# 19_2_Coupled_PP0.net
KiCad netlist of a schematic drawn in Altium Designer
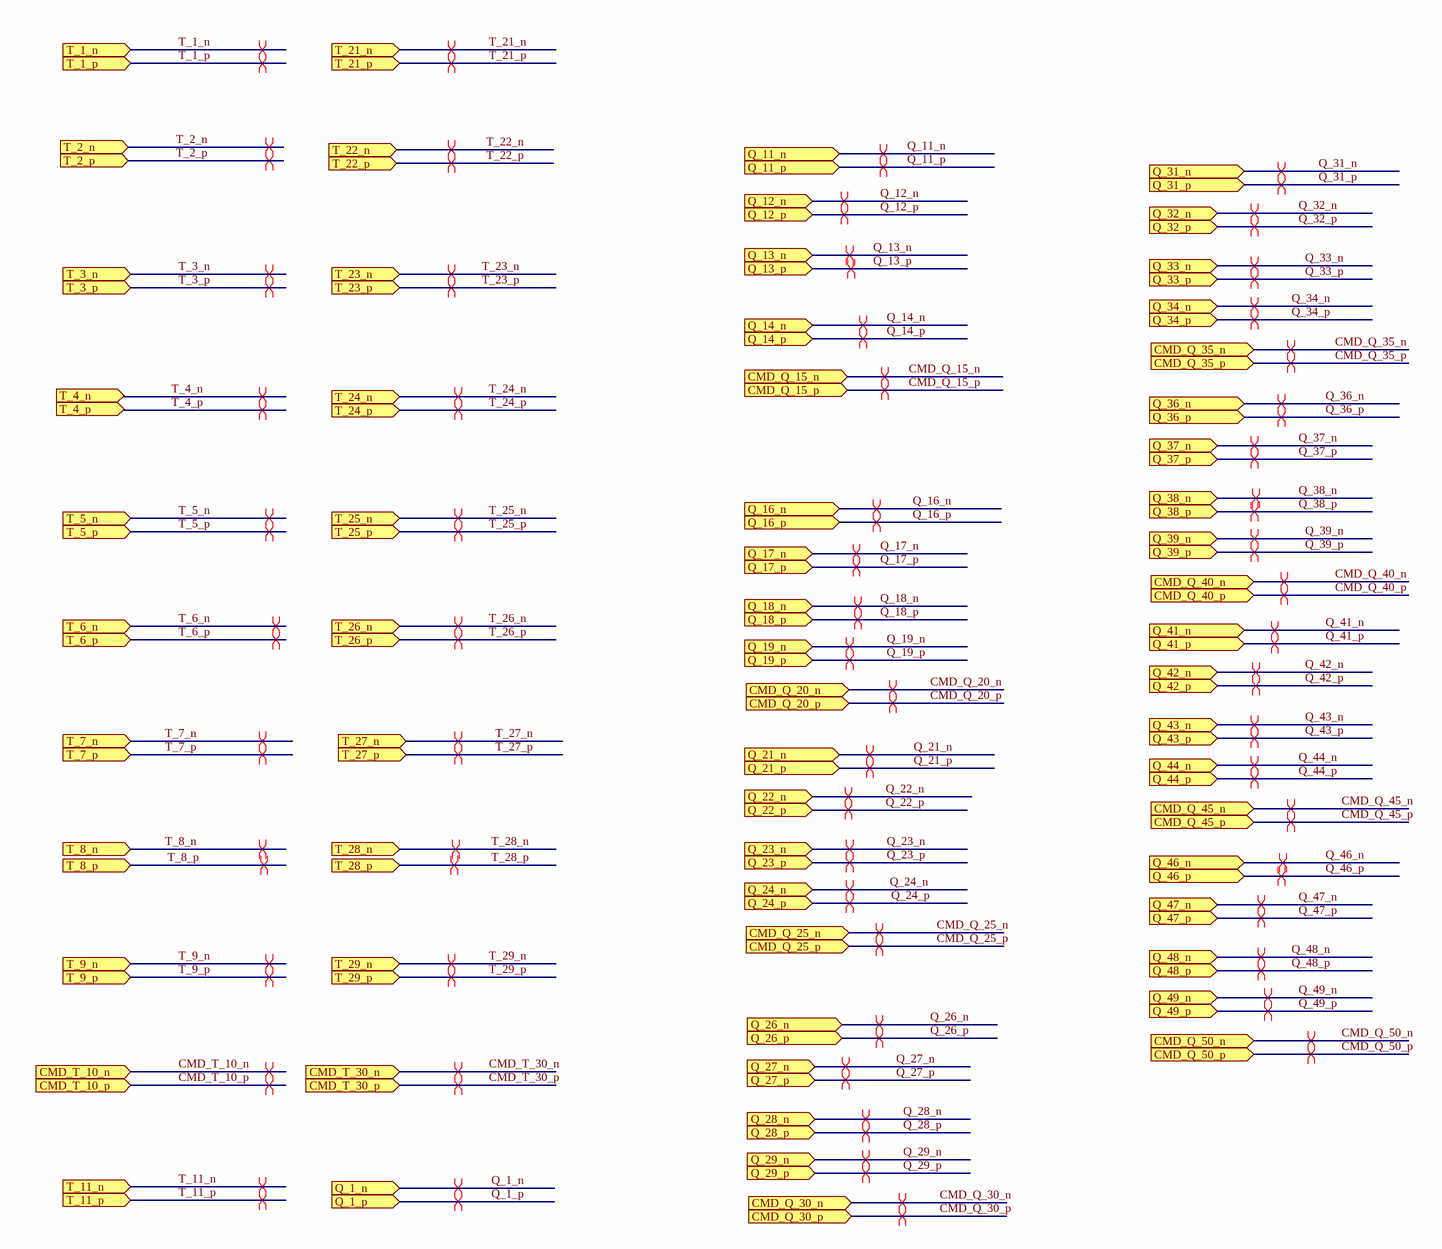
[diagram p0: 19_2_Coupled_PP0.SchDoc, top left]
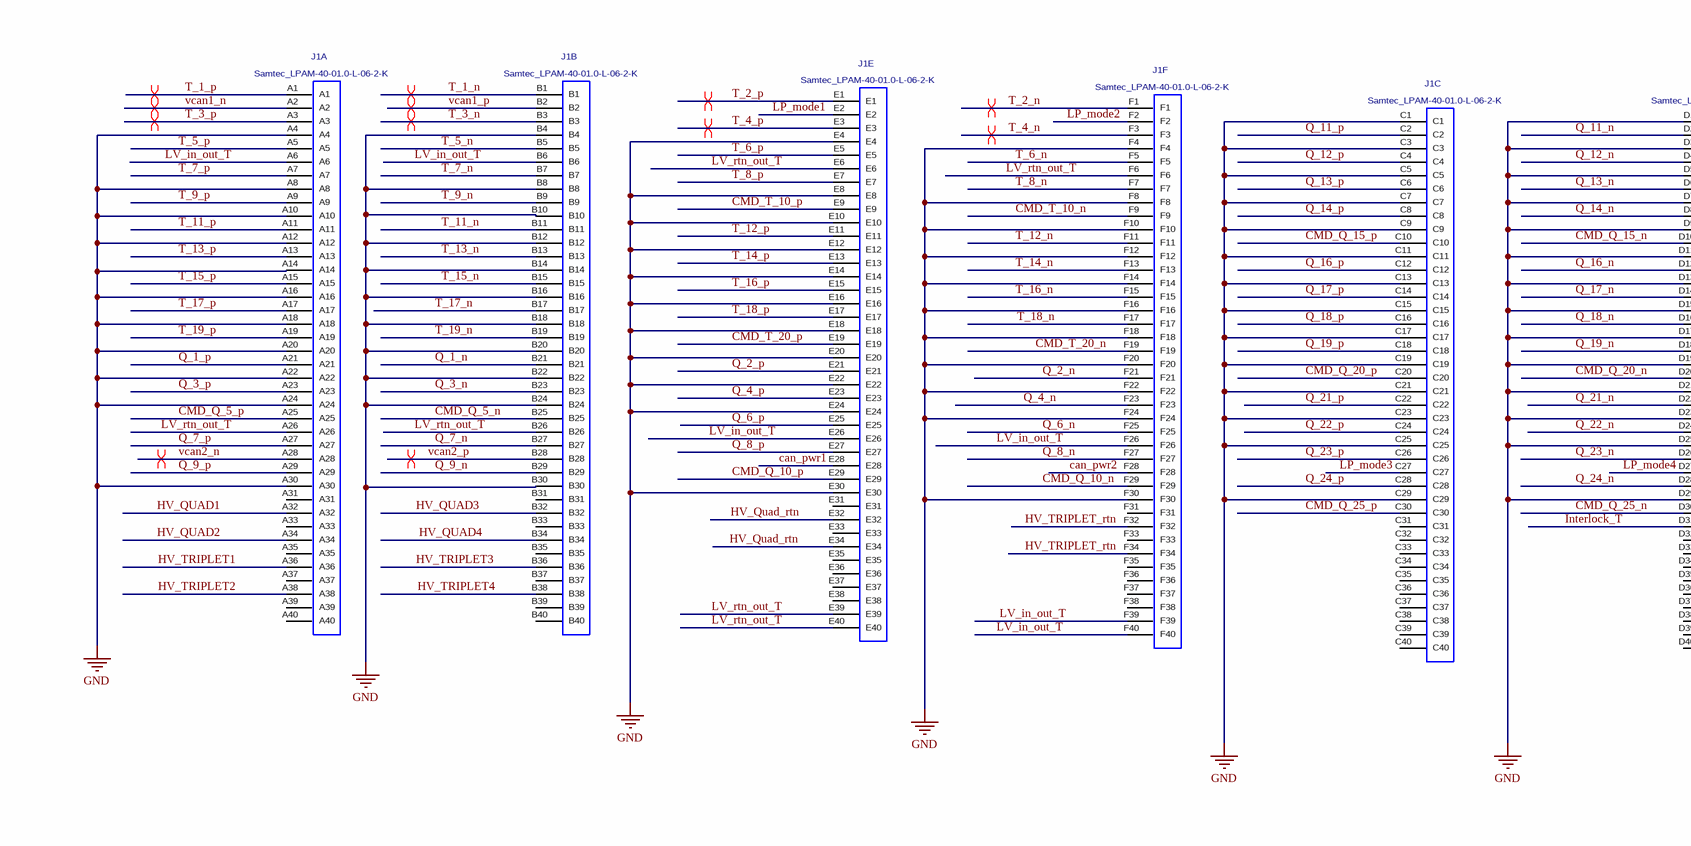
[diagram p1: 19_2_Coupled_PP0.SchDoc, top middle]
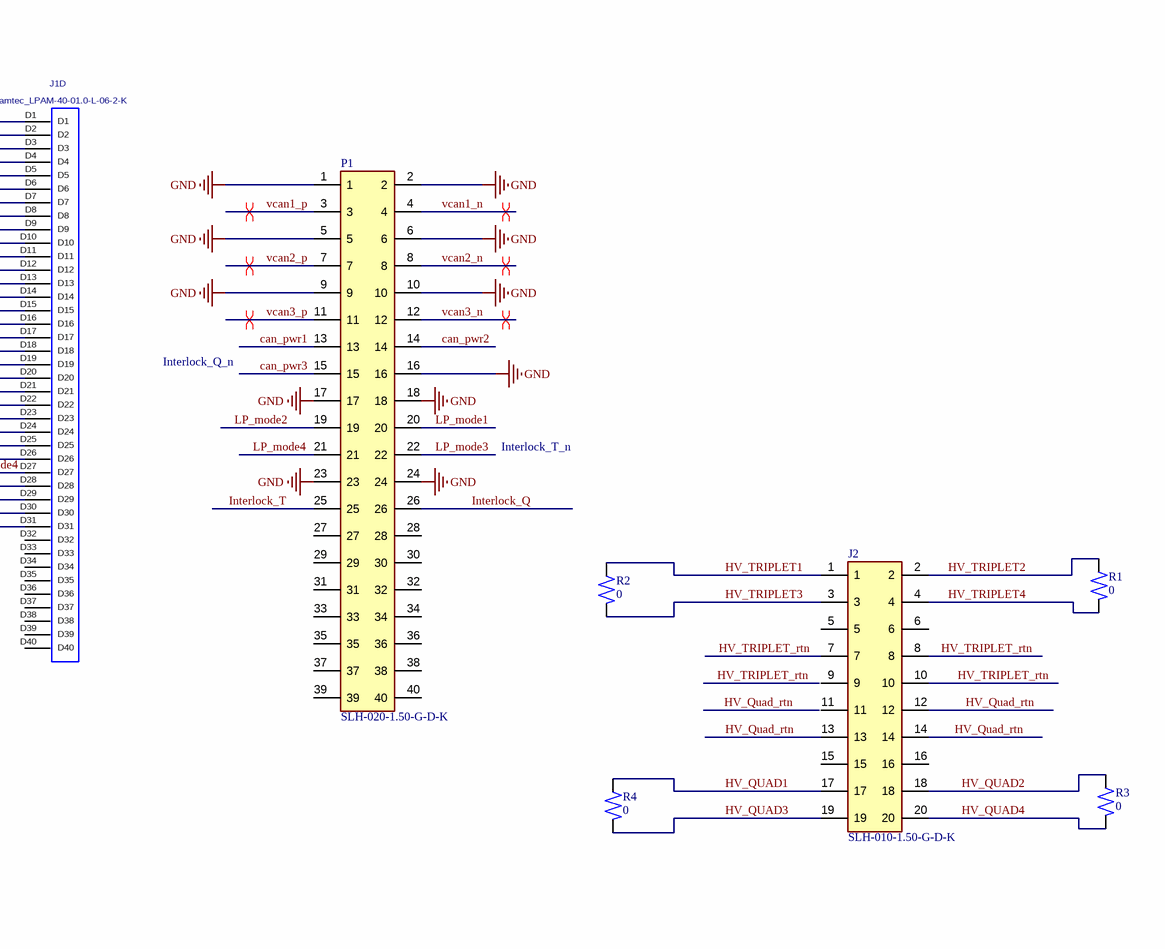
[diagram p2: 19_2_Coupled_PP0.SchDoc, top right]
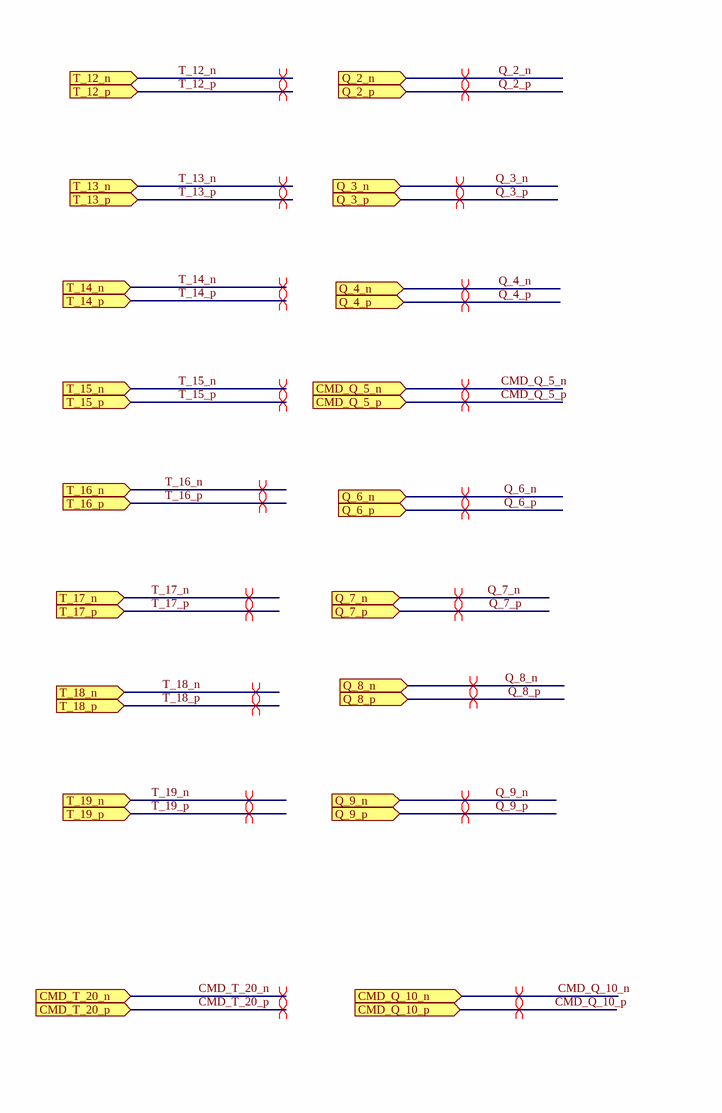
[diagram p3: 19_2_Coupled_PP0.SchDoc, bottom left]
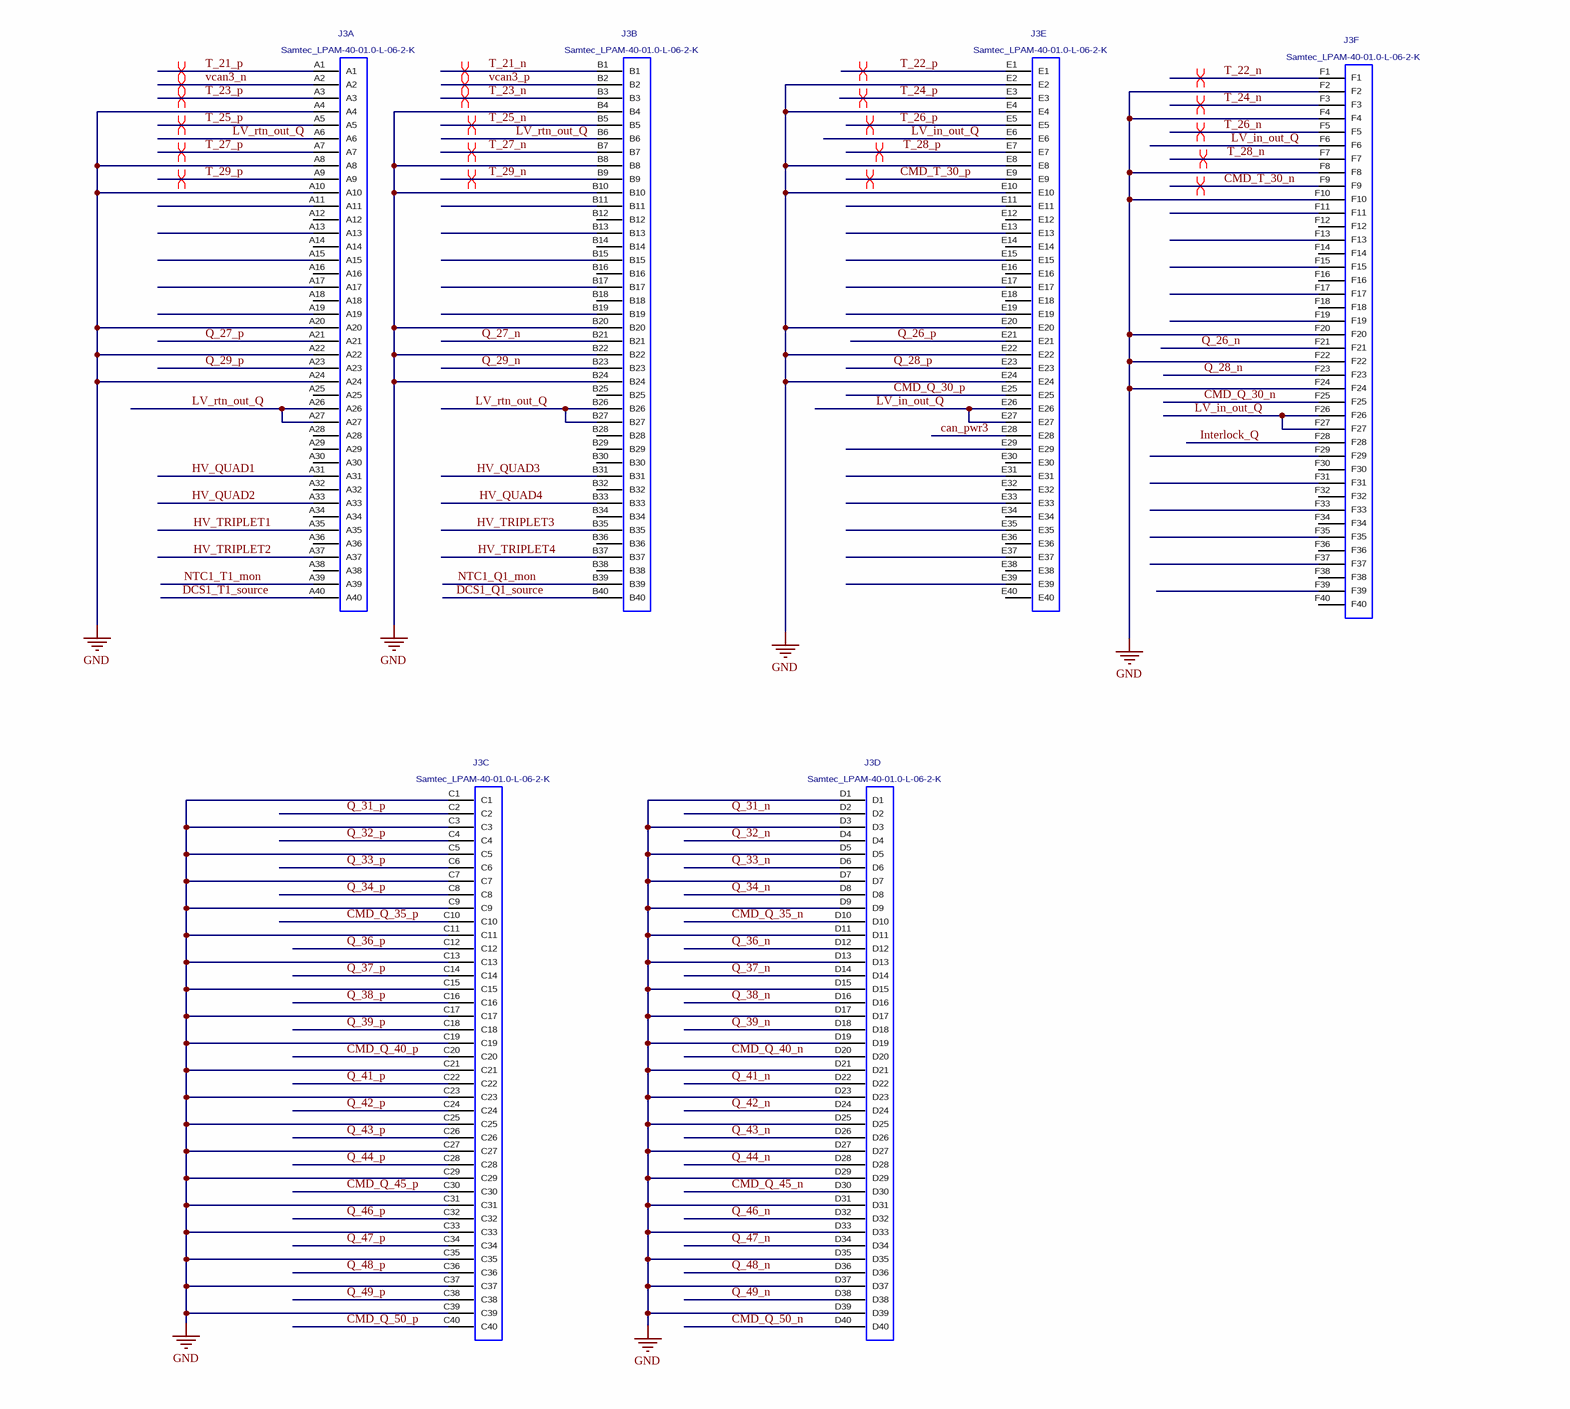
[diagram p4: 19_2_Coupled_PP0.SchDoc, bottom middle]
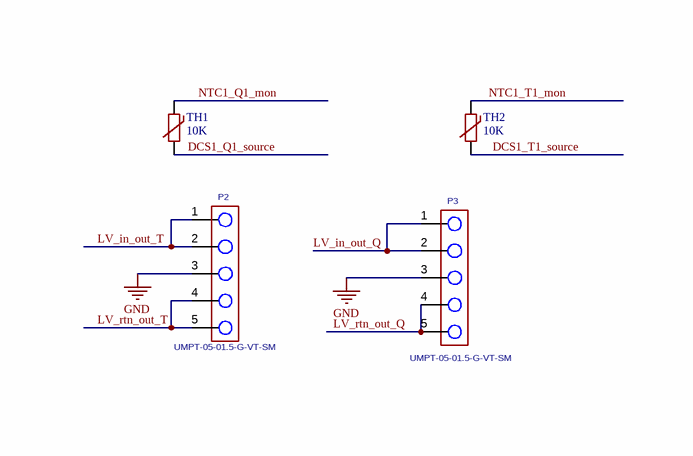
[diagram p5: 19_2_Coupled_PP0.SchDoc, bottom right]

(export (version "E")
  (design (tool "Eeschema 10.0.6"))
  (components
    (comp (ref "J1")
      (value "Samtec_LPAM-40-01.0-L-06-2-K")
      (footprint "Samtec_LPAM_240Pin_V")
      (description "Samtec; LPAM-40-01.0-L-06-2-K, Connector 240Pin Male, LPAM_240Pin_V")
      (fields
        (field (name "MANUFACTURER") "SAMTEC")
        (field (name "MANUFACTURER PART NUMBER") "LPAM-04-01.0-L-06-2-K")
      )
      (libsource (lib "yee_sch_lib") (part "Samtec_LPAM-40-01.0-L-06-2-K"))
    )
    (comp (ref "J2")
      (value "SLH-010-1.50-G-D-K")
      (footprint "Samtec_SLH-010-1.50-G-D-K")
      (description "Samtec; SLH-010-1.50-G-D-K, Connetor 20-Pin SMD")
      (fields
        (field (name "MANUFACTURER") "Samtec")
        (field (name "MANUFACTURER PART NUMBER") "SLH-010-1.50-G-D-K")
      )
      (libsource (lib "Atlas_stave") (part "Samtec_SLH-010-1.50-G-D-K"))
    )
    (comp (ref "J3")
      (value "Samtec_LPAM-40-01.0-L-06-2-K")
      (footprint "Samtec_LPAM_240Pin_V")
      (description "Samtec; LPAM-40-01.0-L-06-2-K, Connector 240Pin Male, LPAM_240Pin_V")
      (fields
        (field (name "MANUFACTURER") "SAMTEC")
        (field (name "MANUFACTURER PART NUMBER") "LPAM-04-01.0-L-06-2-K")
      )
      (libsource (lib "yee_sch_lib") (part "Samtec_LPAM-40-01.0-L-06-2-K"))
    )
    (comp (ref "P1")
      (value "SLH-020-1.50-G-D-K")
      (footprint "Samtec_SLH-020-1.50-G-D-K")
      (description "Samtec; SLH-020-1.50-G-D-K, Connetor 40-Pin SMD")
      (fields
        (field (name "MANUFACTURER") "Samtec")
        (field (name "MANUFACTURER PART NUMBER") "SLH-020-1.50-G-D-K")
      )
      (libsource (lib "Atlas_stave") (part "Samtec_SLH-020-1.50-G-D-K"))
    )
    (comp (ref "P2")
      (value "UMPT-05-01.5-G-VT-SM")
      (footprint "Samtec_UMPT_5P_V")
      (description "Samtec; UMPT-05-01.5-G-VT-SM, Male Connector 5-Pin, UMPT_5P_V")
      (fields (field (name "MANUFACTURER") "SAMTEC"))
      (libsource (lib "yee_sch_lib") (part "Samtec_UMPT-05-01.5-G-VT-SM"))
    )
    (comp (ref "P3")
      (value "UMPT-05-01.5-G-VT-SM")
      (footprint "Samtec_UMPT_5P_V")
      (description "Samtec; UMPT-05-01.5-G-VT-SM, Male Connector 5-Pin, UMPT_5P_V")
      (fields (field (name "MANUFACTURER") "SAMTEC"))
      (libsource (lib "yee_sch_lib") (part "Samtec_UMPT-05-01.5-G-VT-SM"))
    )
    (comp (ref "R1")
      (value "0")
      (footprint "SM0402")
      (description "Vishay; CRCW04020000Z0ED, CHIP RESISTOR, 0 OHMS 1%, SM0402")
      (fields
        (field (name "MANUFACTURER") "VISHAY")
        (field (name "MANUFACTURER PART NUMBER") "CRCW04020000Z0ED")
      )
      (libsource (lib "yee_sch_lib") (part "R04020000"))
    )
    (comp (ref "R2")
      (value "0")
      (footprint "SM0402")
      (description "Vishay; CRCW04020000Z0ED, CHIP RESISTOR, 0 OHMS 1%, SM0402")
      (fields
        (field (name "MANUFACTURER") "VISHAY")
        (field (name "MANUFACTURER PART NUMBER") "CRCW04020000Z0ED")
      )
      (libsource (lib "yee_sch_lib") (part "R04020000"))
    )
    (comp (ref "R3")
      (value "0")
      (footprint "SM0402")
      (description "Vishay; CRCW04020000Z0ED, CHIP RESISTOR, 0 OHMS 1%, SM0402")
      (fields
        (field (name "MANUFACTURER") "VISHAY")
        (field (name "MANUFACTURER PART NUMBER") "CRCW04020000Z0ED")
      )
      (libsource (lib "yee_sch_lib") (part "R04020000"))
    )
    (comp (ref "R4")
      (value "0")
      (footprint "SM0402")
      (description "Vishay; CRCW04020000Z0ED, CHIP RESISTOR, 0 OHMS 1%, SM0402")
      (fields
        (field (name "MANUFACTURER") "VISHAY")
        (field (name "MANUFACTURER PART NUMBER") "CRCW04020000Z0ED")
      )
      (libsource (lib "yee_sch_lib") (part "R04020000"))
    )
    (comp (ref "TH1")
      (value "10K")
      (footprint "SM0805")
      (description "TE; NTC0805J10K, Thermister NTC 10K 5% 2-Pin, SM0805")
      (fields
        (field (name "MANUFACTURER") "TE Connectivity")
        (field (name "MANUFACTURER PART NUMBER") "NTC0805J10K")
      )
      (libsource (lib "yee_sch_lib") (part "NTC080510K0"))
    )
    (comp (ref "TH2")
      (value "10K")
      (footprint "SM0805")
      (description "TE; NTC0805J10K, Thermister NTC 10K 5% 2-Pin, SM0805")
      (fields
        (field (name "MANUFACTURER") "TE Connectivity")
        (field (name "MANUFACTURER PART NUMBER") "NTC0805J10K")
      )
      (libsource (lib "yee_sch_lib") (part "NTC080510K0"))
    )
  )
  (nets
    (net (code "1") (name "/CMD_Q_5_n") (class "Default")
      (node (ref "J1") (pin "B25") (pinfunction "B25_B25") (pintype "passive"))
    )
    (net (code "2") (name "/CMD_Q_5_p") (class "Default")
      (node (ref "J1") (pin "A25") (pinfunction "A25_A25") (pintype "passive"))
    )
    (net (code "3") (name "/CMD_Q_10_n") (class "Default")
      (node (ref "J1") (pin "F29") (pinfunction "F29_F29") (pintype "passive"))
    )
    (net (code "4") (name "/CMD_Q_10_p") (class "Default")
      (node (ref "J1") (pin "E29") (pinfunction "E29_E29") (pintype "passive"))
    )
    (net (code "5") (name "/CMD_Q_15_n") (class "Default")
      (node (ref "J1") (pin "D10") (pinfunction "D10_D10") (pintype "passive"))
    )
    (net (code "6") (name "/CMD_Q_15_p") (class "Default")
      (node (ref "J1") (pin "C10") (pinfunction "C10_C10") (pintype "passive"))
    )
    (net (code "7") (name "/CMD_Q_20_n") (class "Default")
      (node (ref "J1") (pin "D20") (pinfunction "D20_D20") (pintype "passive"))
    )
    (net (code "8") (name "/CMD_Q_20_p") (class "Default")
      (node (ref "J1") (pin "C20") (pinfunction "C20_C20") (pintype "passive"))
    )
    (net (code "9") (name "/CMD_Q_25_n") (class "Default")
      (node (ref "J1") (pin "D30") (pinfunction "D30_D30") (pintype "passive"))
    )
    (net (code "10") (name "/CMD_Q_25_p") (class "Default")
      (node (ref "J1") (pin "C30") (pinfunction "C30_C30") (pintype "passive"))
    )
    (net (code "11") (name "/CMD_Q_30_n") (class "Default")
      (node (ref "J3") (pin "F25") (pinfunction "F25_F25") (pintype "passive"))
    )
    (net (code "12") (name "/CMD_Q_30_p") (class "Default")
      (node (ref "J3") (pin "E25") (pinfunction "E25_E25") (pintype "passive"))
    )
    (net (code "13") (name "/CMD_Q_35_n") (class "Default")
      (node (ref "J3") (pin "D10") (pinfunction "D10_D10") (pintype "passive"))
    )
    (net (code "14") (name "/CMD_Q_35_p") (class "Default")
      (node (ref "J3") (pin "C10") (pinfunction "C10_C10") (pintype "passive"))
    )
    (net (code "15") (name "/CMD_Q_40_n") (class "Default")
      (node (ref "J3") (pin "D20") (pinfunction "D20_D20") (pintype "passive"))
    )
    (net (code "16") (name "/CMD_Q_40_p") (class "Default")
      (node (ref "J3") (pin "C20") (pinfunction "C20_C20") (pintype "passive"))
    )
    (net (code "17") (name "/CMD_Q_45_n") (class "Default")
      (node (ref "J3") (pin "D30") (pinfunction "D30_D30") (pintype "passive"))
    )
    (net (code "18") (name "/CMD_Q_45_p") (class "Default")
      (node (ref "J3") (pin "C30") (pinfunction "C30_C30") (pintype "passive"))
    )
    (net (code "19") (name "/CMD_Q_50_n") (class "Default")
      (node (ref "J3") (pin "D40") (pinfunction "D40_D40") (pintype "passive"))
    )
    (net (code "20") (name "/CMD_Q_50_p") (class "Default")
      (node (ref "J3") (pin "C40") (pinfunction "C40_C40") (pintype "passive"))
    )
    (net (code "21") (name "/CMD_T_10_n") (class "Default")
      (node (ref "J1") (pin "F9") (pinfunction "F9_F9") (pintype "passive"))
    )
    (net (code "22") (name "/CMD_T_10_p") (class "Default")
      (node (ref "J1") (pin "E9") (pinfunction "E9_E9") (pintype "passive"))
    )
    (net (code "23") (name "/CMD_T_20_n") (class "Default")
      (node (ref "J1") (pin "F19") (pinfunction "F19_F19") (pintype "passive"))
    )
    (net (code "24") (name "/CMD_T_20_p") (class "Default")
      (node (ref "J1") (pin "E19") (pinfunction "E19_E19") (pintype "passive"))
    )
    (net (code "25") (name "/CMD_T_30_n") (class "Default")
      (node (ref "J3") (pin "F9") (pinfunction "F9_F9") (pintype "passive"))
    )
    (net (code "26") (name "/CMD_T_30_p") (class "Default")
      (node (ref "J3") (pin "E9") (pinfunction "E9_E9") (pintype "passive"))
    )
    (net (code "27") (name "/DCS1_Q1_source") (class "Default")
      (node (ref "J3") (pin "B40") (pinfunction "B40_B40") (pintype "passive"))
      (node (ref "TH1") (pin "2") (pinfunction "N2_2") (pintype "passive"))
    )
    (net (code "28") (name "/DCS1_T1_source") (class "Default")
      (node (ref "J3") (pin "A40") (pinfunction "A40_A40") (pintype "passive"))
      (node (ref "TH2") (pin "2") (pinfunction "N2_2") (pintype "passive"))
    )
    (net (code "29") (name "/HV_QUAD1") (class "Default")
      (node (ref "J1") (pin "A32") (pinfunction "A32_A32") (pintype "passive"))
      (node (ref "J2") (pin "17") (pinfunction "17_17") (pintype "passive"))
      (node (ref "J3") (pin "A31") (pinfunction "A31_A31") (pintype "passive"))
      (node (ref "R4") (pin "1") (pinfunction "N1_1") (pintype "passive"))
    )
    (net (code "30") (name "/HV_QUAD2") (class "Default")
      (node (ref "J1") (pin "A34") (pinfunction "A34_A34") (pintype "passive"))
      (node (ref "J2") (pin "18") (pinfunction "18_18") (pintype "passive"))
      (node (ref "J3") (pin "A33") (pinfunction "A33_A33") (pintype "passive"))
      (node (ref "R3") (pin "1") (pinfunction "N1_1") (pintype "passive"))
    )
    (net (code "31") (name "/HV_QUAD3") (class "Default")
      (node (ref "J1") (pin "B32") (pinfunction "B32_B32") (pintype "passive"))
      (node (ref "J2") (pin "19") (pinfunction "19_19") (pintype "passive"))
      (node (ref "J3") (pin "B31") (pinfunction "B31_B31") (pintype "passive"))
      (node (ref "R4") (pin "2") (pinfunction "N2_2") (pintype "passive"))
    )
    (net (code "32") (name "/HV_QUAD4") (class "Default")
      (node (ref "J1") (pin "B34") (pinfunction "B34_B34") (pintype "passive"))
      (node (ref "J2") (pin "20") (pinfunction "20_20") (pintype "passive"))
      (node (ref "J3") (pin "B33") (pinfunction "B33_B33") (pintype "passive"))
      (node (ref "R3") (pin "2") (pinfunction "N2_2") (pintype "passive"))
    )
    (net (code "33") (name "/HV_Quad_rtn") (class "Default")
      (node (ref "J1") (pin "E32") (pinfunction "E32_E32") (pintype "passive"))
      (node (ref "J1") (pin "E34") (pinfunction "E34_E34") (pintype "passive"))
      (node (ref "J2") (pin "12") (pinfunction "12_12") (pintype "passive"))
      (node (ref "J2") (pin "13") (pinfunction "13_13") (pintype "passive"))
      (node (ref "J2") (pin "14") (pinfunction "14_14") (pintype "passive"))
    )
    (net (code "34") (name "/HV_TRIPLET1") (class "Default")
      (node (ref "J1") (pin "A36") (pinfunction "A36_A36") (pintype "passive"))
      (node (ref "J2") (pin "1") (pinfunction "1_1") (pintype "passive"))
      (node (ref "J3") (pin "A35") (pinfunction "A35_A35") (pintype "passive"))
      (node (ref "R2") (pin "1") (pinfunction "N1_1") (pintype "passive"))
    )
    (net (code "35") (name "/HV_TRIPLET2") (class "Default")
      (node (ref "J1") (pin "A38") (pinfunction "A38_A38") (pintype "passive"))
      (node (ref "J2") (pin "2") (pinfunction "2_2") (pintype "tri_state"))
      (node (ref "J3") (pin "A37") (pinfunction "A37_A37") (pintype "passive"))
      (node (ref "R1") (pin "1") (pinfunction "N1_1") (pintype "passive"))
    )
    (net (code "36") (name "/HV_TRIPLET3") (class "Default")
      (node (ref "J1") (pin "B36") (pinfunction "B36_B36") (pintype "passive"))
      (node (ref "J2") (pin "3") (pinfunction "3_3") (pintype "passive"))
      (node (ref "J3") (pin "B35") (pinfunction "B35_B35") (pintype "passive"))
      (node (ref "R2") (pin "2") (pinfunction "N2_2") (pintype "passive"))
    )
    (net (code "37") (name "/HV_TRIPLET4") (class "Default")
      (node (ref "J1") (pin "B38") (pinfunction "B38_B38") (pintype "passive"))
      (node (ref "J2") (pin "4") (pinfunction "4_4") (pintype "passive"))
      (node (ref "J3") (pin "B37") (pinfunction "B37_B37") (pintype "passive"))
      (node (ref "R1") (pin "2") (pinfunction "N2_2") (pintype "passive"))
    )
    (net (code "38") (name "/HV_TRIPLET_rtn") (class "Default")
      (node (ref "J1") (pin "F32") (pinfunction "F32_F32") (pintype "passive"))
      (node (ref "J1") (pin "F34") (pinfunction "F34_F34") (pintype "passive"))
      (node (ref "J2") (pin "10") (pinfunction "10_10") (pintype "passive"))
      (node (ref "J2") (pin "7") (pinfunction "7_7") (pintype "passive"))
      (node (ref "J2") (pin "8") (pinfunction "8_8") (pintype "passive"))
    )
    (net (code "39") (name "/Interlock_Q") (class "Default")
      (node (ref "J3") (pin "F28") (pinfunction "F28_F28") (pintype "passive"))
      (node (ref "P1") (pin "26") (pinfunction "26_26") (pintype "passive"))
    )
    (net (code "40") (name "/Interlock_T") (class "Default")
      (node (ref "J1") (pin "D31") (pinfunction "D31_D31") (pintype "passive"))
      (node (ref "P1") (pin "25") (pinfunction "25_25") (pintype "passive"))
    )
    (net (code "41") (name "/LP_mode1") (class "Default")
      (node (ref "J1") (pin "E2") (pinfunction "E2_E2") (pintype "passive"))
      (node (ref "P1") (pin "20") (pinfunction "20_20") (pintype "passive"))
    )
    (net (code "42") (name "/LP_mode2") (class "Default")
      (node (ref "J1") (pin "F2") (pinfunction "F2_F2") (pintype "passive"))
      (node (ref "P1") (pin "19") (pinfunction "19_19") (pintype "passive"))
    )
    (net (code "43") (name "/LP_mode3") (class "Default")
      (node (ref "J1") (pin "C27") (pinfunction "C27_C27") (pintype "passive"))
      (node (ref "P1") (pin "22") (pinfunction "22_22") (pintype "passive"))
    )
    (net (code "44") (name "/LP_mode4") (class "Default")
      (node (ref "J1") (pin "D27") (pinfunction "D27_D27") (pintype "passive"))
      (node (ref "P1") (pin "21") (pinfunction "21_21") (pintype "passive"))
    )
    (net (code "45") (name "/LV_in_out_Q") (class "Default")
      (node (ref "J3") (pin "E26") (pinfunction "E26_E26") (pintype "passive"))
      (node (ref "J3") (pin "E27") (pinfunction "E27_E27") (pintype "passive"))
      (node (ref "J3") (pin "E6") (pinfunction "E6_E6") (pintype "passive"))
      (node (ref "J3") (pin "F26") (pinfunction "F26_F26") (pintype "passive"))
      (node (ref "J3") (pin "F27") (pinfunction "F27_F27") (pintype "passive"))
      (node (ref "J3") (pin "F6") (pinfunction "F6_F6") (pintype "passive"))
      (node (ref "P3") (pin "1") (pinfunction "1_1") (pintype "passive"))
      (node (ref "P3") (pin "2") (pinfunction "2_2") (pintype "passive"))
    )
    (net (code "46") (name "/LV_in_out_T") (class "Default")
      (node (ref "J1") (pin "A6") (pinfunction "A6_A6") (pintype "passive"))
      (node (ref "J1") (pin "B6") (pinfunction "B6_B6") (pintype "passive"))
      (node (ref "J1") (pin "E26") (pinfunction "E26_E26") (pintype "passive"))
      (node (ref "J1") (pin "F26") (pinfunction "F26_F26") (pintype "passive"))
      (node (ref "J1") (pin "F39") (pinfunction "F39_F39") (pintype "passive"))
      (node (ref "J1") (pin "F40") (pinfunction "F40_F40") (pintype "passive"))
      (node (ref "P2") (pin "1") (pinfunction "1_1") (pintype "passive"))
      (node (ref "P2") (pin "2") (pinfunction "2_2") (pintype "passive"))
    )
    (net (code "47") (name "/LV_rtn_out_Q") (class "Default")
      (node (ref "J3") (pin "A26") (pinfunction "A26_A26") (pintype "passive"))
      (node (ref "J3") (pin "A27") (pinfunction "A27_A27") (pintype "passive"))
      (node (ref "J3") (pin "A6") (pinfunction "A6_A6") (pintype "passive"))
      (node (ref "J3") (pin "B26") (pinfunction "B26_B26") (pintype "passive"))
      (node (ref "J3") (pin "B27") (pinfunction "B27_B27") (pintype "passive"))
      (node (ref "J3") (pin "B6") (pinfunction "B6_B6") (pintype "passive"))
      (node (ref "P3") (pin "4") (pinfunction "4_4") (pintype "passive"))
      (node (ref "P3") (pin "5") (pinfunction "5_5") (pintype "passive"))
    )
    (net (code "48") (name "/LV_rtn_out_T") (class "Default")
      (node (ref "J1") (pin "A26") (pinfunction "A26_A26") (pintype "passive"))
      (node (ref "J1") (pin "B26") (pinfunction "B26_B26") (pintype "passive"))
      (node (ref "J1") (pin "E39") (pinfunction "E39_E39") (pintype "passive"))
      (node (ref "J1") (pin "E40") (pinfunction "E40_E40") (pintype "passive"))
      (node (ref "J1") (pin "E6") (pinfunction "E6_E6") (pintype "passive"))
      (node (ref "J1") (pin "F6") (pinfunction "F6_F6") (pintype "passive"))
      (node (ref "P2") (pin "4") (pinfunction "4_4") (pintype "passive"))
      (node (ref "P2") (pin "5") (pinfunction "5_5") (pintype "passive"))
    )
    (net (code "49") (name "/NTC1_Q1_mon") (class "Default")
      (node (ref "J3") (pin "B39") (pinfunction "B39_B39") (pintype "passive"))
      (node (ref "TH1") (pin "1") (pinfunction "N1_1") (pintype "passive"))
    )
    (net (code "50") (name "/NTC1_T1_mon") (class "Default")
      (node (ref "J3") (pin "A39") (pinfunction "A39_A39") (pintype "passive"))
      (node (ref "TH2") (pin "1") (pinfunction "N1_1") (pintype "passive"))
    )
    (net (code "51") (name "/Q_1_n") (class "Default")
      (node (ref "J1") (pin "B21") (pinfunction "B21_B21") (pintype "passive"))
    )
    (net (code "52") (name "/Q_1_p") (class "Default")
      (node (ref "J1") (pin "A21") (pinfunction "A21_A21") (pintype "passive"))
    )
    (net (code "53") (name "/Q_2_n") (class "Default")
      (node (ref "J1") (pin "F21") (pinfunction "F21_F21") (pintype "passive"))
    )
    (net (code "54") (name "/Q_2_p") (class "Default")
      (node (ref "J1") (pin "E21") (pinfunction "E21_E21") (pintype "passive"))
    )
    (net (code "55") (name "/Q_3_n") (class "Default")
      (node (ref "J1") (pin "B23") (pinfunction "B23_B23") (pintype "passive"))
    )
    (net (code "56") (name "/Q_3_p") (class "Default")
      (node (ref "J1") (pin "A23") (pinfunction "A23_A23") (pintype "passive"))
    )
    (net (code "57") (name "/Q_4_n") (class "Default")
      (node (ref "J1") (pin "F23") (pinfunction "F23_F23") (pintype "passive"))
    )
    (net (code "58") (name "/Q_4_p") (class "Default")
      (node (ref "J1") (pin "E23") (pinfunction "E23_E23") (pintype "passive"))
    )
    (net (code "59") (name "/Q_6_n") (class "Default")
      (node (ref "J1") (pin "F25") (pinfunction "F25_F25") (pintype "passive"))
    )
    (net (code "60") (name "/Q_6_p") (class "Default")
      (node (ref "J1") (pin "E25") (pinfunction "E25_E25") (pintype "passive"))
    )
    (net (code "61") (name "/Q_7_n") (class "Default")
      (node (ref "J1") (pin "B27") (pinfunction "B27_B27") (pintype "passive"))
    )
    (net (code "62") (name "/Q_7_p") (class "Default")
      (node (ref "J1") (pin "A27") (pinfunction "A27_A27") (pintype "passive"))
    )
    (net (code "63") (name "/Q_8_n") (class "Default")
      (node (ref "J1") (pin "F27") (pinfunction "F27_F27") (pintype "passive"))
    )
    (net (code "64") (name "/Q_8_p") (class "Default")
      (node (ref "J1") (pin "E27") (pinfunction "E27_E27") (pintype "passive"))
    )
    (net (code "65") (name "/Q_9_n") (class "Default")
      (node (ref "J1") (pin "B29") (pinfunction "B29_B29") (pintype "passive"))
    )
    (net (code "66") (name "/Q_9_p") (class "Default")
      (node (ref "J1") (pin "A29") (pinfunction "A29_A29") (pintype "passive"))
    )
    (net (code "67") (name "/Q_11_n") (class "Default")
      (node (ref "J1") (pin "D2") (pinfunction "D2_D2") (pintype "passive"))
    )
    (net (code "68") (name "/Q_11_p") (class "Default")
      (node (ref "J1") (pin "C2") (pinfunction "C2_C2") (pintype "passive"))
    )
    (net (code "69") (name "/Q_12_n") (class "Default")
      (node (ref "J1") (pin "D4") (pinfunction "D4_D4") (pintype "passive"))
    )
    (net (code "70") (name "/Q_12_p") (class "Default")
      (node (ref "J1") (pin "C4") (pinfunction "C4_C4") (pintype "passive"))
    )
    (net (code "71") (name "/Q_13_n") (class "Default")
      (node (ref "J1") (pin "D6") (pinfunction "D6_D6") (pintype "passive"))
    )
    (net (code "72") (name "/Q_13_p") (class "Default")
      (node (ref "J1") (pin "C6") (pinfunction "C6_C6") (pintype "passive"))
    )
    (net (code "73") (name "/Q_14_n") (class "Default")
      (node (ref "J1") (pin "D8") (pinfunction "D8_D8") (pintype "passive"))
    )
    (net (code "74") (name "/Q_14_p") (class "Default")
      (node (ref "J1") (pin "C8") (pinfunction "C8_C8") (pintype "passive"))
    )
    (net (code "75") (name "/Q_16_n") (class "Default")
      (node (ref "J1") (pin "D12") (pinfunction "D12_D12") (pintype "passive"))
    )
    (net (code "76") (name "/Q_16_p") (class "Default")
      (node (ref "J1") (pin "C12") (pinfunction "C12_C12") (pintype "passive"))
    )
    (net (code "77") (name "/Q_17_n") (class "Default")
      (node (ref "J1") (pin "D14") (pinfunction "D14_D14") (pintype "passive"))
    )
    (net (code "78") (name "/Q_17_p") (class "Default")
      (node (ref "J1") (pin "C14") (pinfunction "C14_C14") (pintype "passive"))
    )
    (net (code "79") (name "/Q_18_n") (class "Default")
      (node (ref "J1") (pin "D16") (pinfunction "D16_D16") (pintype "passive"))
    )
    (net (code "80") (name "/Q_18_p") (class "Default")
      (node (ref "J1") (pin "C16") (pinfunction "C16_C16") (pintype "passive"))
    )
    (net (code "81") (name "/Q_19_n") (class "Default")
      (node (ref "J1") (pin "D18") (pinfunction "D18_D18") (pintype "passive"))
    )
    (net (code "82") (name "/Q_19_p") (class "Default")
      (node (ref "J1") (pin "C18") (pinfunction "C18_C18") (pintype "passive"))
    )
    (net (code "83") (name "/Q_21_n") (class "Default")
      (node (ref "J1") (pin "D22") (pinfunction "D22_D22") (pintype "passive"))
    )
    (net (code "84") (name "/Q_21_p") (class "Default")
      (node (ref "J1") (pin "C22") (pinfunction "C22_C22") (pintype "passive"))
    )
    (net (code "85") (name "/Q_22_n") (class "Default")
      (node (ref "J1") (pin "D24") (pinfunction "D24_D24") (pintype "passive"))
    )
    (net (code "86") (name "/Q_22_p") (class "Default")
      (node (ref "J1") (pin "C24") (pinfunction "C24_C24") (pintype "passive"))
    )
    (net (code "87") (name "/Q_23_n") (class "Default")
      (node (ref "J1") (pin "D26") (pinfunction "D26_D26") (pintype "passive"))
    )
    (net (code "88") (name "/Q_23_p") (class "Default")
      (node (ref "J1") (pin "C26") (pinfunction "C26_C26") (pintype "passive"))
    )
    (net (code "89") (name "/Q_24_n") (class "Default")
      (node (ref "J1") (pin "D28") (pinfunction "D28_D28") (pintype "passive"))
    )
    (net (code "90") (name "/Q_24_p") (class "Default")
      (node (ref "J1") (pin "C28") (pinfunction "C28_C28") (pintype "passive"))
    )
    (net (code "91") (name "/Q_26_n") (class "Default")
      (node (ref "J3") (pin "F21") (pinfunction "F21_F21") (pintype "passive"))
    )
    (net (code "92") (name "/Q_26_p") (class "Default")
      (node (ref "J3") (pin "E21") (pinfunction "E21_E21") (pintype "passive"))
    )
    (net (code "93") (name "/Q_27_n") (class "Default")
      (node (ref "J3") (pin "B21") (pinfunction "B21_B21") (pintype "passive"))
    )
    (net (code "94") (name "/Q_27_p") (class "Default")
      (node (ref "J3") (pin "A21") (pinfunction "A21_A21") (pintype "passive"))
    )
    (net (code "95") (name "/Q_28_n") (class "Default")
      (node (ref "J3") (pin "F23") (pinfunction "F23_F23") (pintype "passive"))
    )
    (net (code "96") (name "/Q_28_p") (class "Default")
      (node (ref "J3") (pin "E23") (pinfunction "E23_E23") (pintype "passive"))
    )
    (net (code "97") (name "/Q_29_n") (class "Default")
      (node (ref "J3") (pin "B23") (pinfunction "B23_B23") (pintype "passive"))
    )
    (net (code "98") (name "/Q_29_p") (class "Default")
      (node (ref "J3") (pin "A23") (pinfunction "A23_A23") (pintype "passive"))
    )
    (net (code "99") (name "/Q_31_n") (class "Default")
      (node (ref "J3") (pin "D2") (pinfunction "D2_D2") (pintype "passive"))
    )
    (net (code "100") (name "/Q_31_p") (class "Default")
      (node (ref "J3") (pin "C2") (pinfunction "C2_C2") (pintype "passive"))
    )
    (net (code "101") (name "/Q_32_n") (class "Default")
      (node (ref "J3") (pin "D4") (pinfunction "D4_D4") (pintype "passive"))
    )
    (net (code "102") (name "/Q_32_p") (class "Default")
      (node (ref "J3") (pin "C4") (pinfunction "C4_C4") (pintype "passive"))
    )
    (net (code "103") (name "/Q_33_n") (class "Default")
      (node (ref "J3") (pin "D6") (pinfunction "D6_D6") (pintype "passive"))
    )
    (net (code "104") (name "/Q_33_p") (class "Default")
      (node (ref "J3") (pin "C6") (pinfunction "C6_C6") (pintype "passive"))
    )
    (net (code "105") (name "/Q_34_n") (class "Default")
      (node (ref "J3") (pin "D8") (pinfunction "D8_D8") (pintype "passive"))
    )
    (net (code "106") (name "/Q_34_p") (class "Default")
      (node (ref "J3") (pin "C8") (pinfunction "C8_C8") (pintype "passive"))
    )
    (net (code "107") (name "/Q_36_n") (class "Default")
      (node (ref "J3") (pin "D12") (pinfunction "D12_D12") (pintype "passive"))
    )
    (net (code "108") (name "/Q_36_p") (class "Default")
      (node (ref "J3") (pin "C12") (pinfunction "C12_C12") (pintype "passive"))
    )
    (net (code "109") (name "/Q_37_n") (class "Default")
      (node (ref "J3") (pin "D14") (pinfunction "D14_D14") (pintype "passive"))
    )
    (net (code "110") (name "/Q_37_p") (class "Default")
      (node (ref "J3") (pin "C14") (pinfunction "C14_C14") (pintype "passive"))
    )
    (net (code "111") (name "/Q_38_n") (class "Default")
      (node (ref "J3") (pin "D16") (pinfunction "D16_D16") (pintype "passive"))
    )
    (net (code "112") (name "/Q_38_p") (class "Default")
      (node (ref "J3") (pin "C16") (pinfunction "C16_C16") (pintype "passive"))
    )
    (net (code "113") (name "/Q_39_n") (class "Default")
      (node (ref "J3") (pin "D18") (pinfunction "D18_D18") (pintype "passive"))
    )
    (net (code "114") (name "/Q_39_p") (class "Default")
      (node (ref "J3") (pin "C18") (pinfunction "C18_C18") (pintype "passive"))
    )
    (net (code "115") (name "/Q_41_n") (class "Default")
      (node (ref "J3") (pin "D22") (pinfunction "D22_D22") (pintype "passive"))
    )
    (net (code "116") (name "/Q_41_p") (class "Default")
      (node (ref "J3") (pin "C22") (pinfunction "C22_C22") (pintype "passive"))
    )
    (net (code "117") (name "/Q_42_n") (class "Default")
      (node (ref "J3") (pin "D24") (pinfunction "D24_D24") (pintype "passive"))
    )
    (net (code "118") (name "/Q_42_p") (class "Default")
      (node (ref "J3") (pin "C24") (pinfunction "C24_C24") (pintype "passive"))
    )
    (net (code "119") (name "/Q_43_n") (class "Default")
      (node (ref "J3") (pin "D26") (pinfunction "D26_D26") (pintype "passive"))
    )
    (net (code "120") (name "/Q_43_p") (class "Default")
      (node (ref "J3") (pin "C26") (pinfunction "C26_C26") (pintype "passive"))
    )
    (net (code "121") (name "/Q_44_n") (class "Default")
      (node (ref "J3") (pin "D28") (pinfunction "D28_D28") (pintype "passive"))
    )
    (net (code "122") (name "/Q_44_p") (class "Default")
      (node (ref "J3") (pin "C28") (pinfunction "C28_C28") (pintype "passive"))
    )
    (net (code "123") (name "/Q_46_n") (class "Default")
      (node (ref "J3") (pin "D32") (pinfunction "D32_D32") (pintype "passive"))
    )
    (net (code "124") (name "/Q_46_p") (class "Default")
      (node (ref "J3") (pin "C32") (pinfunction "C32_C32") (pintype "passive"))
    )
    (net (code "125") (name "/Q_47_n") (class "Default")
      (node (ref "J3") (pin "D34") (pinfunction "D34_D34") (pintype "passive"))
    )
    (net (code "126") (name "/Q_47_p") (class "Default")
      (node (ref "J3") (pin "C34") (pinfunction "C34_C34") (pintype "passive"))
    )
    (net (code "127") (name "/Q_48_n") (class "Default")
      (node (ref "J3") (pin "D36") (pinfunction "D36_D36") (pintype "passive"))
    )
    (net (code "128") (name "/Q_48_p") (class "Default")
      (node (ref "J3") (pin "C36") (pinfunction "C36_C36") (pintype "passive"))
    )
    (net (code "129") (name "/Q_49_n") (class "Default")
      (node (ref "J3") (pin "D38") (pinfunction "D38_D38") (pintype "passive"))
    )
    (net (code "130") (name "/Q_49_p") (class "Default")
      (node (ref "J3") (pin "C38") (pinfunction "C38_C38") (pintype "passive"))
    )
    (net (code "131") (name "/T_1_n") (class "Default")
      (node (ref "J1") (pin "B1") (pinfunction "B1_B1") (pintype "passive"))
    )
    (net (code "132") (name "/T_1_p") (class "Default")
      (node (ref "J1") (pin "A1") (pinfunction "A1_A1") (pintype "passive"))
    )
    (net (code "133") (name "/T_2_n") (class "Default")
      (node (ref "J1") (pin "F1") (pinfunction "F1_F1") (pintype "passive"))
    )
    (net (code "134") (name "/T_2_p") (class "Default")
      (node (ref "J1") (pin "E1") (pinfunction "E1_E1") (pintype "passive"))
    )
    (net (code "135") (name "/T_3_n") (class "Default")
      (node (ref "J1") (pin "B3") (pinfunction "B3_B3") (pintype "passive"))
    )
    (net (code "136") (name "/T_3_p") (class "Default")
      (node (ref "J1") (pin "A3") (pinfunction "A3_A3") (pintype "passive"))
    )
    (net (code "137") (name "/T_4_n") (class "Default")
      (node (ref "J1") (pin "F3") (pinfunction "F3_F3") (pintype "passive"))
    )
    (net (code "138") (name "/T_4_p") (class "Default")
      (node (ref "J1") (pin "E3") (pinfunction "E3_E3") (pintype "passive"))
    )
    (net (code "139") (name "/T_5_n") (class "Default")
      (node (ref "J1") (pin "B5") (pinfunction "B5_B5") (pintype "passive"))
    )
    (net (code "140") (name "/T_5_p") (class "Default")
      (node (ref "J1") (pin "A5") (pinfunction "A5_A5") (pintype "passive"))
    )
    (net (code "141") (name "/T_6_n") (class "Default")
      (node (ref "J1") (pin "F5") (pinfunction "F5_F5") (pintype "passive"))
    )
    (net (code "142") (name "/T_6_p") (class "Default")
      (node (ref "J1") (pin "E5") (pinfunction "E5_E5") (pintype "passive"))
    )
    (net (code "143") (name "/T_7_n") (class "Default")
      (node (ref "J1") (pin "B7") (pinfunction "B7_B7") (pintype "passive"))
    )
    (net (code "144") (name "/T_7_p") (class "Default")
      (node (ref "J1") (pin "A7") (pinfunction "A7_A7") (pintype "passive"))
    )
    (net (code "145") (name "/T_8_n") (class "Default")
      (node (ref "J1") (pin "F7") (pinfunction "F7_F7") (pintype "passive"))
    )
    (net (code "146") (name "/T_8_p") (class "Default")
      (node (ref "J1") (pin "E7") (pinfunction "E7_E7") (pintype "passive"))
    )
    (net (code "147") (name "/T_9_n") (class "Default")
      (node (ref "J1") (pin "B9") (pinfunction "B9_B9") (pintype "passive"))
    )
    (net (code "148") (name "/T_9_p") (class "Default")
      (node (ref "J1") (pin "A9") (pinfunction "A9_A9") (pintype "passive"))
    )
    (net (code "149") (name "/T_11_n") (class "Default")
      (node (ref "J1") (pin "B11") (pinfunction "B11_B11") (pintype "passive"))
    )
    (net (code "150") (name "/T_11_p") (class "Default")
      (node (ref "J1") (pin "A11") (pinfunction "A11_A11") (pintype "passive"))
    )
    (net (code "151") (name "/T_12_n") (class "Default")
      (node (ref "J1") (pin "F11") (pinfunction "F11_F11") (pintype "passive"))
    )
    (net (code "152") (name "/T_12_p") (class "Default")
      (node (ref "J1") (pin "E11") (pinfunction "E11_E11") (pintype "passive"))
    )
    (net (code "153") (name "/T_13_n") (class "Default")
      (node (ref "J1") (pin "B13") (pinfunction "B13_B13") (pintype "passive"))
    )
    (net (code "154") (name "/T_13_p") (class "Default")
      (node (ref "J1") (pin "A13") (pinfunction "A13_A13") (pintype "passive"))
    )
    (net (code "155") (name "/T_14_n") (class "Default")
      (node (ref "J1") (pin "F13") (pinfunction "F13_F13") (pintype "passive"))
    )
    (net (code "156") (name "/T_14_p") (class "Default")
      (node (ref "J1") (pin "E13") (pinfunction "E13_E13") (pintype "passive"))
    )
    (net (code "157") (name "/T_15_n") (class "Default")
      (node (ref "J1") (pin "B15") (pinfunction "B15_B15") (pintype "passive"))
    )
    (net (code "158") (name "/T_15_p") (class "Default")
      (node (ref "J1") (pin "A15") (pinfunction "A15_A15") (pintype "passive"))
    )
    (net (code "159") (name "/T_16_n") (class "Default")
      (node (ref "J1") (pin "F15") (pinfunction "F15_F15") (pintype "passive"))
    )
    (net (code "160") (name "/T_16_p") (class "Default")
      (node (ref "J1") (pin "E15") (pinfunction "E15_E15") (pintype "passive"))
    )
    (net (code "161") (name "/T_17_n") (class "Default")
      (node (ref "J1") (pin "B17") (pinfunction "B17_B17") (pintype "passive"))
    )
    (net (code "162") (name "/T_17_p") (class "Default")
      (node (ref "J1") (pin "A17") (pinfunction "A17_A17") (pintype "passive"))
    )
    (net (code "163") (name "/T_18_n") (class "Default")
      (node (ref "J1") (pin "F17") (pinfunction "F17_F17") (pintype "passive"))
    )
    (net (code "164") (name "/T_18_p") (class "Default")
      (node (ref "J1") (pin "E17") (pinfunction "E17_E17") (pintype "passive"))
    )
    (net (code "165") (name "/T_19_n") (class "Default")
      (node (ref "J1") (pin "B19") (pinfunction "B19_B19") (pintype "passive"))
    )
    (net (code "166") (name "/T_19_p") (class "Default")
      (node (ref "J1") (pin "A19") (pinfunction "A19_A19") (pintype "passive"))
    )
    (net (code "167") (name "/T_21_n") (class "Default")
      (node (ref "J3") (pin "B1") (pinfunction "B1_B1") (pintype "passive"))
    )
    (net (code "168") (name "/T_21_p") (class "Default")
      (node (ref "J3") (pin "A1") (pinfunction "A1_A1") (pintype "passive"))
    )
    (net (code "169") (name "/T_22_n") (class "Default")
      (node (ref "J3") (pin "F1") (pinfunction "F1_F1") (pintype "passive"))
    )
    (net (code "170") (name "/T_22_p") (class "Default")
      (node (ref "J3") (pin "E1") (pinfunction "E1_E1") (pintype "passive"))
    )
    (net (code "171") (name "/T_23_n") (class "Default")
      (node (ref "J3") (pin "B3") (pinfunction "B3_B3") (pintype "passive"))
    )
    (net (code "172") (name "/T_23_p") (class "Default")
      (node (ref "J3") (pin "A3") (pinfunction "A3_A3") (pintype "passive"))
    )
    (net (code "173") (name "/T_24_n") (class "Default")
      (node (ref "J3") (pin "F3") (pinfunction "F3_F3") (pintype "passive"))
    )
    (net (code "174") (name "/T_24_p") (class "Default")
      (node (ref "J3") (pin "E3") (pinfunction "E3_E3") (pintype "passive"))
    )
    (net (code "175") (name "/T_25_n") (class "Default")
      (node (ref "J3") (pin "B5") (pinfunction "B5_B5") (pintype "passive"))
    )
    (net (code "176") (name "/T_25_p") (class "Default")
      (node (ref "J3") (pin "A5") (pinfunction "A5_A5") (pintype "passive"))
    )
    (net (code "177") (name "/T_26_n") (class "Default")
      (node (ref "J3") (pin "F5") (pinfunction "F5_F5") (pintype "passive"))
    )
    (net (code "178") (name "/T_26_p") (class "Default")
      (node (ref "J3") (pin "E5") (pinfunction "E5_E5") (pintype "passive"))
    )
    (net (code "179") (name "/T_27_n") (class "Default")
      (node (ref "J3") (pin "B7") (pinfunction "B7_B7") (pintype "passive"))
    )
    (net (code "180") (name "/T_27_p") (class "Default")
      (node (ref "J3") (pin "A7") (pinfunction "A7_A7") (pintype "passive"))
    )
    (net (code "181") (name "/T_28_n") (class "Default")
      (node (ref "J3") (pin "F7") (pinfunction "F7_F7") (pintype "passive"))
    )
    (net (code "182") (name "/T_28_p") (class "Default")
      (node (ref "J3") (pin "E7") (pinfunction "E7_E7") (pintype "passive"))
    )
    (net (code "183") (name "/T_29_n") (class "Default")
      (node (ref "J3") (pin "B9") (pinfunction "B9_B9") (pintype "passive"))
    )
    (net (code "184") (name "/T_29_p") (class "Default")
      (node (ref "J3") (pin "A9") (pinfunction "A9_A9") (pintype "passive"))
    )
    (net (code "185") (name "/can_pwr1") (class "Default")
      (node (ref "J1") (pin "E28") (pinfunction "E28_E28") (pintype "passive"))
      (node (ref "P1") (pin "13") (pinfunction "13_13") (pintype "passive"))
    )
    (net (code "186") (name "/can_pwr2") (class "Default")
      (node (ref "J1") (pin "F28") (pinfunction "F28_F28") (pintype "passive"))
      (node (ref "P1") (pin "14") (pinfunction "14_14") (pintype "passive"))
    )
    (net (code "187") (name "/can_pwr3") (class "Default")
      (node (ref "J3") (pin "E28") (pinfunction "E28_E28") (pintype "passive"))
      (node (ref "P1") (pin "15") (pinfunction "15_15") (pintype "passive"))
    )
    (net (code "188") (name "/vcan1_n") (class "Default")
      (node (ref "J1") (pin "A2") (pinfunction "A2_A2") (pintype "passive"))
      (node (ref "P1") (pin "4") (pinfunction "4_4") (pintype "passive"))
    )
    (net (code "189") (name "/vcan1_p") (class "Default")
      (node (ref "J1") (pin "B2") (pinfunction "B2_B2") (pintype "passive"))
      (node (ref "P1") (pin "3") (pinfunction "3_3") (pintype "passive"))
    )
    (net (code "190") (name "/vcan2_n") (class "Default")
      (node (ref "J1") (pin "A28") (pinfunction "A28_A28") (pintype "passive"))
      (node (ref "P1") (pin "8") (pinfunction "8_8") (pintype "passive"))
    )
    (net (code "191") (name "/vcan2_p") (class "Default")
      (node (ref "J1") (pin "B28") (pinfunction "B28_B28") (pintype "passive"))
      (node (ref "P1") (pin "7") (pinfunction "7_7") (pintype "passive"))
    )
    (net (code "192") (name "/vcan3_n") (class "Default")
      (node (ref "J3") (pin "A2") (pinfunction "A2_A2") (pintype "passive"))
      (node (ref "P1") (pin "12") (pinfunction "12_12") (pintype "passive"))
    )
    (net (code "193") (name "/vcan3_p") (class "Default")
      (node (ref "J3") (pin "B2") (pinfunction "B2_B2") (pintype "passive"))
      (node (ref "P1") (pin "11") (pinfunction "11_11") (pintype "passive"))
    )
    (net (code "194") (name "GND") (class "Default")
      (node (ref "J1") (pin "A10") (pinfunction "A10_A10") (pintype "passive"))
      (node (ref "J1") (pin "A12") (pinfunction "A12_A12") (pintype "passive"))
      (node (ref "J1") (pin "A14") (pinfunction "A14_A14") (pintype "passive"))
      (node (ref "J1") (pin "A16") (pinfunction "A16_A16") (pintype "passive"))
      (node (ref "J1") (pin "A18") (pinfunction "A18_A18") (pintype "passive"))
      (node (ref "J1") (pin "A20") (pinfunction "A20_A20") (pintype "passive"))
      (node (ref "J1") (pin "A22") (pinfunction "A22_A22") (pintype "passive"))
      (node (ref "J1") (pin "A24") (pinfunction "A24_A24") (pintype "passive"))
      (node (ref "J1") (pin "A30") (pinfunction "A30_A30") (pintype "passive"))
      (node (ref "J1") (pin "A4") (pinfunction "A4_A4") (pintype "passive"))
      (node (ref "J1") (pin "A8") (pinfunction "A8_A8") (pintype "passive"))
      (node (ref "J1") (pin "B10") (pinfunction "B10_B10") (pintype "passive"))
      (node (ref "J1") (pin "B12") (pinfunction "B12_B12") (pintype "passive"))
      (node (ref "J1") (pin "B14") (pinfunction "B14_B14") (pintype "passive"))
      (node (ref "J1") (pin "B16") (pinfunction "B16_B16") (pintype "passive"))
      (node (ref "J1") (pin "B18") (pinfunction "B18_B18") (pintype "passive"))
      (node (ref "J1") (pin "B20") (pinfunction "B20_B20") (pintype "passive"))
      (node (ref "J1") (pin "B22") (pinfunction "B22_B22") (pintype "passive"))
      (node (ref "J1") (pin "B24") (pinfunction "B24_B24") (pintype "passive"))
      (node (ref "J1") (pin "B30") (pinfunction "B30_B30") (pintype "passive"))
      (node (ref "J1") (pin "B4") (pinfunction "B4_B4") (pintype "passive"))
      (node (ref "J1") (pin "B8") (pinfunction "B8_B8") (pintype "passive"))
      (node (ref "J1") (pin "C1") (pinfunction "C1_C1") (pintype "passive"))
      (node (ref "J1") (pin "C11") (pinfunction "C11_C11") (pintype "passive"))
      (node (ref "J1") (pin "C13") (pinfunction "C13_C13") (pintype "passive"))
      (node (ref "J1") (pin "C15") (pinfunction "C15_C15") (pintype "passive"))
      (node (ref "J1") (pin "C17") (pinfunction "C17_C17") (pintype "passive"))
      (node (ref "J1") (pin "C19") (pinfunction "C19_C19") (pintype "passive"))
      (node (ref "J1") (pin "C21") (pinfunction "C21_C21") (pintype "passive"))
      (node (ref "J1") (pin "C23") (pinfunction "C23_C23") (pintype "passive"))
      (node (ref "J1") (pin "C25") (pinfunction "C25_C25") (pintype "passive"))
      (node (ref "J1") (pin "C29") (pinfunction "C29_C29") (pintype "passive"))
      (node (ref "J1") (pin "C3") (pinfunction "C3_C3") (pintype "passive"))
      (node (ref "J1") (pin "C5") (pinfunction "C5_C5") (pintype "passive"))
      (node (ref "J1") (pin "C7") (pinfunction "C7_C7") (pintype "passive"))
      (node (ref "J1") (pin "C9") (pinfunction "C9_C9") (pintype "passive"))
      (node (ref "J1") (pin "D1") (pinfunction "D1_D1") (pintype "passive"))
      (node (ref "J1") (pin "D11") (pinfunction "D11_D11") (pintype "passive"))
      (node (ref "J1") (pin "D13") (pinfunction "D13_D13") (pintype "passive"))
      (node (ref "J1") (pin "D15") (pinfunction "D15_D15") (pintype "passive"))
      (node (ref "J1") (pin "D17") (pinfunction "D17_D17") (pintype "passive"))
      (node (ref "J1") (pin "D19") (pinfunction "D19_D19") (pintype "passive"))
      (node (ref "J1") (pin "D21") (pinfunction "D21_D21") (pintype "passive"))
      (node (ref "J1") (pin "D23") (pinfunction "D23_D23") (pintype "passive"))
      (node (ref "J1") (pin "D25") (pinfunction "D25_D25") (pintype "passive"))
      (node (ref "J1") (pin "D29") (pinfunction "D29_D29") (pintype "passive"))
      (node (ref "J1") (pin "D3") (pinfunction "D3_D3") (pintype "passive"))
      (node (ref "J1") (pin "D5") (pinfunction "D5_D5") (pintype "passive"))
      (node (ref "J1") (pin "D7") (pinfunction "D7_D7") (pintype "passive"))
      (node (ref "J1") (pin "D9") (pinfunction "D9_D9") (pintype "passive"))
      (node (ref "J1") (pin "E10") (pinfunction "E10_E10") (pintype "passive"))
      (node (ref "J1") (pin "E12") (pinfunction "E12_E12") (pintype "passive"))
      (node (ref "J1") (pin "E14") (pinfunction "E14_E14") (pintype "passive"))
      (node (ref "J1") (pin "E16") (pinfunction "E16_E16") (pintype "passive"))
      (node (ref "J1") (pin "E18") (pinfunction "E18_E18") (pintype "passive"))
      (node (ref "J1") (pin "E20") (pinfunction "E20_E20") (pintype "passive"))
      (node (ref "J1") (pin "E22") (pinfunction "E22_E22") (pintype "passive"))
      (node (ref "J1") (pin "E24") (pinfunction "E24_E24") (pintype "passive"))
      (node (ref "J1") (pin "E30") (pinfunction "E30_E30") (pintype "passive"))
      (node (ref "J1") (pin "E4") (pinfunction "E4_E4") (pintype "passive"))
      (node (ref "J1") (pin "E8") (pinfunction "E8_E8") (pintype "passive"))
      (node (ref "J1") (pin "F10") (pinfunction "F10_F10") (pintype "passive"))
      (node (ref "J1") (pin "F12") (pinfunction "F12_F12") (pintype "passive"))
      (node (ref "J1") (pin "F14") (pinfunction "F14_F14") (pintype "passive"))
      (node (ref "J1") (pin "F16") (pinfunction "F16_F16") (pintype "passive"))
      (node (ref "J1") (pin "F18") (pinfunction "F18_F18") (pintype "passive"))
      (node (ref "J1") (pin "F20") (pinfunction "F20_F20") (pintype "passive"))
      (node (ref "J1") (pin "F22") (pinfunction "F22_F22") (pintype "passive"))
      (node (ref "J1") (pin "F24") (pinfunction "F24_F24") (pintype "passive"))
      (node (ref "J1") (pin "F30") (pinfunction "F30_F30") (pintype "passive"))
      (node (ref "J1") (pin "F4") (pinfunction "F4_F4") (pintype "passive"))
      (node (ref "J1") (pin "F8") (pinfunction "F8_F8") (pintype "passive"))
      (node (ref "J3") (pin "A10") (pinfunction "A10_A10") (pintype "passive"))
      (node (ref "J3") (pin "A20") (pinfunction "A20_A20") (pintype "passive"))
      (node (ref "J3") (pin "A22") (pinfunction "A22_A22") (pintype "passive"))
      (node (ref "J3") (pin "A24") (pinfunction "A24_A24") (pintype "passive"))
      (node (ref "J3") (pin "A4") (pinfunction "A4_A4") (pintype "passive"))
      (node (ref "J3") (pin "A8") (pinfunction "A8_A8") (pintype "passive"))
      (node (ref "J3") (pin "B10") (pinfunction "B10_B10") (pintype "passive"))
      (node (ref "J3") (pin "B20") (pinfunction "B20_B20") (pintype "passive"))
      (node (ref "J3") (pin "B22") (pinfunction "B22_B22") (pintype "passive"))
      (node (ref "J3") (pin "B24") (pinfunction "B24_B24") (pintype "passive"))
      (node (ref "J3") (pin "B4") (pinfunction "B4_B4") (pintype "passive"))
      (node (ref "J3") (pin "B8") (pinfunction "B8_B8") (pintype "passive"))
      (node (ref "J3") (pin "C1") (pinfunction "C1_C1") (pintype "passive"))
      (node (ref "J3") (pin "C11") (pinfunction "C11_C11") (pintype "passive"))
      (node (ref "J3") (pin "C13") (pinfunction "C13_C13") (pintype "passive"))
      (node (ref "J3") (pin "C15") (pinfunction "C15_C15") (pintype "passive"))
      (node (ref "J3") (pin "C17") (pinfunction "C17_C17") (pintype "passive"))
      (node (ref "J3") (pin "C19") (pinfunction "C19_C19") (pintype "passive"))
      (node (ref "J3") (pin "C21") (pinfunction "C21_C21") (pintype "passive"))
      (node (ref "J3") (pin "C23") (pinfunction "C23_C23") (pintype "passive"))
      (node (ref "J3") (pin "C25") (pinfunction "C25_C25") (pintype "passive"))
      (node (ref "J3") (pin "C27") (pinfunction "C27_C27") (pintype "passive"))
      (node (ref "J3") (pin "C29") (pinfunction "C29_C29") (pintype "passive"))
      (node (ref "J3") (pin "C3") (pinfunction "C3_C3") (pintype "passive"))
      (node (ref "J3") (pin "C31") (pinfunction "C31_C31") (pintype "passive"))
      (node (ref "J3") (pin "C33") (pinfunction "C33_C33") (pintype "passive"))
      (node (ref "J3") (pin "C35") (pinfunction "C35_C35") (pintype "passive"))
      (node (ref "J3") (pin "C37") (pinfunction "C37_C37") (pintype "passive"))
      (node (ref "J3") (pin "C39") (pinfunction "C39_C39") (pintype "passive"))
      (node (ref "J3") (pin "C5") (pinfunction "C5_C5") (pintype "passive"))
      (node (ref "J3") (pin "C7") (pinfunction "C7_C7") (pintype "passive"))
      (node (ref "J3") (pin "C9") (pinfunction "C9_C9") (pintype "passive"))
      (node (ref "J3") (pin "D1") (pinfunction "D1_D1") (pintype "passive"))
      (node (ref "J3") (pin "D11") (pinfunction "D11_D11") (pintype "passive"))
      (node (ref "J3") (pin "D13") (pinfunction "D13_D13") (pintype "passive"))
      (node (ref "J3") (pin "D15") (pinfunction "D15_D15") (pintype "passive"))
      (node (ref "J3") (pin "D17") (pinfunction "D17_D17") (pintype "passive"))
      (node (ref "J3") (pin "D19") (pinfunction "D19_D19") (pintype "passive"))
      (node (ref "J3") (pin "D21") (pinfunction "D21_D21") (pintype "passive"))
      (node (ref "J3") (pin "D23") (pinfunction "D23_D23") (pintype "passive"))
      (node (ref "J3") (pin "D25") (pinfunction "D25_D25") (pintype "passive"))
      (node (ref "J3") (pin "D27") (pinfunction "D27_D27") (pintype "passive"))
      (node (ref "J3") (pin "D29") (pinfunction "D29_D29") (pintype "passive"))
      (node (ref "J3") (pin "D3") (pinfunction "D3_D3") (pintype "passive"))
      (node (ref "J3") (pin "D31") (pinfunction "D31_D31") (pintype "passive"))
      (node (ref "J3") (pin "D33") (pinfunction "D33_D33") (pintype "passive"))
      (node (ref "J3") (pin "D35") (pinfunction "D35_D35") (pintype "passive"))
      (node (ref "J3") (pin "D37") (pinfunction "D37_D37") (pintype "passive"))
      (node (ref "J3") (pin "D39") (pinfunction "D39_D39") (pintype "passive"))
      (node (ref "J3") (pin "D5") (pinfunction "D5_D5") (pintype "passive"))
      (node (ref "J3") (pin "D7") (pinfunction "D7_D7") (pintype "passive"))
      (node (ref "J3") (pin "D9") (pinfunction "D9_D9") (pintype "passive"))
      (node (ref "J3") (pin "E10") (pinfunction "E10_E10") (pintype "passive"))
      (node (ref "J3") (pin "E2") (pinfunction "E2_E2") (pintype "passive"))
      (node (ref "J3") (pin "E20") (pinfunction "E20_E20") (pintype "passive"))
      (node (ref "J3") (pin "E22") (pinfunction "E22_E22") (pintype "passive"))
      (node (ref "J3") (pin "E24") (pinfunction "E24_E24") (pintype "passive"))
      (node (ref "J3") (pin "E4") (pinfunction "E4_E4") (pintype "passive"))
      (node (ref "J3") (pin "E8") (pinfunction "E8_E8") (pintype "passive"))
      (node (ref "J3") (pin "F10") (pinfunction "F10_F10") (pintype "passive"))
      (node (ref "J3") (pin "F2") (pinfunction "F2_F2") (pintype "passive"))
      (node (ref "J3") (pin "F20") (pinfunction "F20_F20") (pintype "passive"))
      (node (ref "J3") (pin "F22") (pinfunction "F22_F22") (pintype "passive"))
      (node (ref "J3") (pin "F24") (pinfunction "F24_F24") (pintype "passive"))
      (node (ref "J3") (pin "F4") (pinfunction "F4_F4") (pintype "passive"))
      (node (ref "J3") (pin "F8") (pinfunction "F8_F8") (pintype "passive"))
      (node (ref "P1") (pin "1") (pinfunction "1_1") (pintype "passive"))
      (node (ref "P1") (pin "10") (pinfunction "10_10") (pintype "passive"))
      (node (ref "P1") (pin "16") (pinfunction "16_16") (pintype "passive"))
      (node (ref "P1") (pin "17") (pinfunction "17_17") (pintype "passive"))
      (node (ref "P1") (pin "18") (pinfunction "18_18") (pintype "passive"))
      (node (ref "P1") (pin "2") (pinfunction "2_2") (pintype "passive"))
      (node (ref "P1") (pin "23") (pinfunction "23_23") (pintype "passive"))
      (node (ref "P1") (pin "24") (pinfunction "24_24") (pintype "passive"))
      (node (ref "P1") (pin "5") (pinfunction "5_5") (pintype "passive"))
      (node (ref "P1") (pin "6") (pinfunction "6_6") (pintype "power_in"))
      (node (ref "P1") (pin "9") (pinfunction "9_9") (pintype "passive"))
      (node (ref "P2") (pin "3") (pinfunction "3_3") (pintype "passive"))
      (node (ref "P3") (pin "3") (pinfunction "3_3") (pintype "passive"))
    )
    (net (code "195") (name "unconnected-(J1-PadA31)") (class "Default")
      (node (ref "J1") (pin "A31") (pinfunction "A31_A31") (pintype "passive"))
    )
    (net (code "196") (name "unconnected-(J1-PadA33)") (class "Default")
      (node (ref "J1") (pin "A33") (pinfunction "A33_A33") (pintype "passive"))
    )
    (net (code "197") (name "unconnected-(J1-PadA35)") (class "Default")
      (node (ref "J1") (pin "A35") (pinfunction "A35_A35") (pintype "passive"))
    )
    (net (code "198") (name "unconnected-(J1-PadA37)") (class "Default")
      (node (ref "J1") (pin "A37") (pinfunction "A37_A37") (pintype "passive"))
    )
    (net (code "199") (name "unconnected-(J1-PadA39)") (class "Default")
      (node (ref "J1") (pin "A39") (pinfunction "A39_A39") (pintype "passive"))
    )
    (net (code "200") (name "unconnected-(J1-PadA40)") (class "Default")
      (node (ref "J1") (pin "A40") (pinfunction "A40_A40") (pintype "passive"))
    )
    (net (code "201") (name "unconnected-(J1-PadB31)") (class "Default")
      (node (ref "J1") (pin "B31") (pinfunction "B31_B31") (pintype "passive"))
    )
    (net (code "202") (name "unconnected-(J1-PadB33)") (class "Default")
      (node (ref "J1") (pin "B33") (pinfunction "B33_B33") (pintype "passive"))
    )
    (net (code "203") (name "unconnected-(J1-PadB35)") (class "Default")
      (node (ref "J1") (pin "B35") (pinfunction "B35_B35") (pintype "passive"))
    )
    (net (code "204") (name "unconnected-(J1-PadB37)") (class "Default")
      (node (ref "J1") (pin "B37") (pinfunction "B37_B37") (pintype "passive"))
    )
    (net (code "205") (name "unconnected-(J1-PadB39)") (class "Default")
      (node (ref "J1") (pin "B39") (pinfunction "B39_B39") (pintype "passive"))
    )
    (net (code "206") (name "unconnected-(J1-PadB40)") (class "Default")
      (node (ref "J1") (pin "B40") (pinfunction "B40_B40") (pintype "passive"))
    )
    (net (code "207") (name "unconnected-(J1-PadC31)") (class "Default")
      (node (ref "J1") (pin "C31") (pinfunction "C31_C31") (pintype "passive"))
    )
    (net (code "208") (name "unconnected-(J1-PadC32)") (class "Default")
      (node (ref "J1") (pin "C32") (pinfunction "C32_C32") (pintype "passive"))
    )
    (net (code "209") (name "unconnected-(J1-PadC33)") (class "Default")
      (node (ref "J1") (pin "C33") (pinfunction "C33_C33") (pintype "passive"))
    )
    (net (code "210") (name "unconnected-(J1-PadC34)") (class "Default")
      (node (ref "J1") (pin "C34") (pinfunction "C34_C34") (pintype "passive"))
    )
    (net (code "211") (name "unconnected-(J1-PadC35)") (class "Default")
      (node (ref "J1") (pin "C35") (pinfunction "C35_C35") (pintype "passive"))
    )
    (net (code "212") (name "unconnected-(J1-PadC36)") (class "Default")
      (node (ref "J1") (pin "C36") (pinfunction "C36_C36") (pintype "passive"))
    )
    (net (code "213") (name "unconnected-(J1-PadC37)") (class "Default")
      (node (ref "J1") (pin "C37") (pinfunction "C37_C37") (pintype "passive"))
    )
    (net (code "214") (name "unconnected-(J1-PadC38)") (class "Default")
      (node (ref "J1") (pin "C38") (pinfunction "C38_C38") (pintype "passive"))
    )
    (net (code "215") (name "unconnected-(J1-PadC39)") (class "Default")
      (node (ref "J1") (pin "C39") (pinfunction "C39_C39") (pintype "passive"))
    )
    (net (code "216") (name "unconnected-(J1-PadC40)") (class "Default")
      (node (ref "J1") (pin "C40") (pinfunction "C40_C40") (pintype "passive"))
    )
    (net (code "217") (name "unconnected-(J1-PadD32)") (class "Default")
      (node (ref "J1") (pin "D32") (pinfunction "D32_D32") (pintype "passive"))
    )
    (net (code "218") (name "unconnected-(J1-PadD33)") (class "Default")
      (node (ref "J1") (pin "D33") (pinfunction "D33_D33") (pintype "passive"))
    )
    (net (code "219") (name "unconnected-(J1-PadD34)") (class "Default")
      (node (ref "J1") (pin "D34") (pinfunction "D34_D34") (pintype "passive"))
    )
    (net (code "220") (name "unconnected-(J1-PadD35)") (class "Default")
      (node (ref "J1") (pin "D35") (pinfunction "D35_D35") (pintype "passive"))
    )
    (net (code "221") (name "unconnected-(J1-PadD36)") (class "Default")
      (node (ref "J1") (pin "D36") (pinfunction "D36_D36") (pintype "passive"))
    )
    (net (code "222") (name "unconnected-(J1-PadD37)") (class "Default")
      (node (ref "J1") (pin "D37") (pinfunction "D37_D37") (pintype "passive"))
    )
    (net (code "223") (name "unconnected-(J1-PadD38)") (class "Default")
      (node (ref "J1") (pin "D38") (pinfunction "D38_D38") (pintype "passive"))
    )
    (net (code "224") (name "unconnected-(J1-PadD39)") (class "Default")
      (node (ref "J1") (pin "D39") (pinfunction "D39_D39") (pintype "passive"))
    )
    (net (code "225") (name "unconnected-(J1-PadD40)") (class "Default")
      (node (ref "J1") (pin "D40") (pinfunction "D40_D40") (pintype "passive"))
    )
    (net (code "226") (name "unconnected-(J1-PadE31)") (class "Default")
      (node (ref "J1") (pin "E31") (pinfunction "E31_E31") (pintype "passive"))
    )
    (net (code "227") (name "unconnected-(J1-PadE33)") (class "Default")
      (node (ref "J1") (pin "E33") (pinfunction "E33_E33") (pintype "passive"))
    )
    (net (code "228") (name "unconnected-(J1-PadE35)") (class "Default")
      (node (ref "J1") (pin "E35") (pinfunction "E35_E35") (pintype "passive"))
    )
    (net (code "229") (name "unconnected-(J1-PadE36)") (class "Default")
      (node (ref "J1") (pin "E36") (pinfunction "E36_E36") (pintype "passive"))
    )
    (net (code "230") (name "unconnected-(J1-PadE37)") (class "Default")
      (node (ref "J1") (pin "E37") (pinfunction "E37_E37") (pintype "passive"))
    )
    (net (code "231") (name "unconnected-(J1-PadE38)") (class "Default")
      (node (ref "J1") (pin "E38") (pinfunction "E38_E38") (pintype "passive"))
    )
    (net (code "232") (name "unconnected-(J1-PadF31)") (class "Default")
      (node (ref "J1") (pin "F31") (pinfunction "F31_F31") (pintype "passive"))
    )
    (net (code "233") (name "unconnected-(J1-PadF33)") (class "Default")
      (node (ref "J1") (pin "F33") (pinfunction "F33_F33") (pintype "passive"))
    )
    (net (code "234") (name "unconnected-(J1-PadF35)") (class "Default")
      (node (ref "J1") (pin "F35") (pinfunction "F35_F35") (pintype "passive"))
    )
    (net (code "235") (name "unconnected-(J1-PadF36)") (class "Default")
      (node (ref "J1") (pin "F36") (pinfunction "F36_F36") (pintype "passive"))
    )
    (net (code "236") (name "unconnected-(J1-PadF37)") (class "Default")
      (node (ref "J1") (pin "F37") (pinfunction "F37_F37") (pintype "passive"))
    )
    (net (code "237") (name "unconnected-(J1-PadF38)") (class "Default")
      (node (ref "J1") (pin "F38") (pinfunction "F38_F38") (pintype "passive"))
    )
    (net (code "238") (name "unconnected-(J2-Pad5)") (class "Default")
      (node (ref "J2") (pin "5") (pinfunction "5_5") (pintype "passive"))
    )
    (net (code "239") (name "unconnected-(J2-Pad6)") (class "Default")
      (node (ref "J2") (pin "6") (pinfunction "6_6") (pintype "passive"))
    )
    (net (code "240") (name "unconnected-(J2-Pad9)") (class "Default")
      (node (ref "J2") (pin "9") (pinfunction "9_9") (pintype "passive"))
    )
    (net (code "241") (name "unconnected-(J2-Pad11)") (class "Default")
      (node (ref "J2") (pin "11") (pinfunction "11_11") (pintype "passive"))
    )
    (net (code "242") (name "unconnected-(J2-Pad15)") (class "Default")
      (node (ref "J2") (pin "15") (pinfunction "15_15") (pintype "passive"))
    )
    (net (code "243") (name "unconnected-(J2-Pad16)") (class "Default")
      (node (ref "J2") (pin "16") (pinfunction "16_16") (pintype "passive"))
    )
    (net (code "244") (name "unconnected-(J3-PadA11)") (class "Default")
      (node (ref "J3") (pin "A11") (pinfunction "A11_A11") (pintype "passive"))
    )
    (net (code "245") (name "unconnected-(J3-PadA12)") (class "Default")
      (node (ref "J3") (pin "A12") (pinfunction "A12_A12") (pintype "passive"))
    )
    (net (code "246") (name "unconnected-(J3-PadA13)") (class "Default")
      (node (ref "J3") (pin "A13") (pinfunction "A13_A13") (pintype "passive"))
    )
    (net (code "247") (name "unconnected-(J3-PadA14)") (class "Default")
      (node (ref "J3") (pin "A14") (pinfunction "A14_A14") (pintype "passive"))
    )
    (net (code "248") (name "unconnected-(J3-PadA15)") (class "Default")
      (node (ref "J3") (pin "A15") (pinfunction "A15_A15") (pintype "passive"))
    )
    (net (code "249") (name "unconnected-(J3-PadA16)") (class "Default")
      (node (ref "J3") (pin "A16") (pinfunction "A16_A16") (pintype "passive"))
    )
    (net (code "250") (name "unconnected-(J3-PadA17)") (class "Default")
      (node (ref "J3") (pin "A17") (pinfunction "A17_A17") (pintype "passive"))
    )
    (net (code "251") (name "unconnected-(J3-PadA18)") (class "Default")
      (node (ref "J3") (pin "A18") (pinfunction "A18_A18") (pintype "passive"))
    )
    (net (code "252") (name "unconnected-(J3-PadA19)") (class "Default")
      (node (ref "J3") (pin "A19") (pinfunction "A19_A19") (pintype "passive"))
    )
    (net (code "253") (name "unconnected-(J3-PadA25)") (class "Default")
      (node (ref "J3") (pin "A25") (pinfunction "A25_A25") (pintype "passive"))
    )
    (net (code "254") (name "unconnected-(J3-PadA28)") (class "Default")
      (node (ref "J3") (pin "A28") (pinfunction "A28_A28") (pintype "passive"))
    )
    (net (code "255") (name "unconnected-(J3-PadA29)") (class "Default")
      (node (ref "J3") (pin "A29") (pinfunction "A29_A29") (pintype "passive"))
    )
    (net (code "256") (name "unconnected-(J3-PadA30)") (class "Default")
      (node (ref "J3") (pin "A30") (pinfunction "A30_A30") (pintype "passive"))
    )
    (net (code "257") (name "unconnected-(J3-PadA32)") (class "Default")
      (node (ref "J3") (pin "A32") (pinfunction "A32_A32") (pintype "passive"))
    )
    (net (code "258") (name "unconnected-(J3-PadA34)") (class "Default")
      (node (ref "J3") (pin "A34") (pinfunction "A34_A34") (pintype "passive"))
    )
    (net (code "259") (name "unconnected-(J3-PadA36)") (class "Default")
      (node (ref "J3") (pin "A36") (pinfunction "A36_A36") (pintype "passive"))
    )
    (net (code "260") (name "unconnected-(J3-PadA38)") (class "Default")
      (node (ref "J3") (pin "A38") (pinfunction "A38_A38") (pintype "passive"))
    )
    (net (code "261") (name "unconnected-(J3-PadB11)") (class "Default")
      (node (ref "J3") (pin "B11") (pinfunction "B11_B11") (pintype "passive"))
    )
    (net (code "262") (name "unconnected-(J3-PadB12)") (class "Default")
      (node (ref "J3") (pin "B12") (pinfunction "B12_B12") (pintype "passive"))
    )
    (net (code "263") (name "unconnected-(J3-PadB13)") (class "Default")
      (node (ref "J3") (pin "B13") (pinfunction "B13_B13") (pintype "passive"))
    )
    (net (code "264") (name "unconnected-(J3-PadB14)") (class "Default")
      (node (ref "J3") (pin "B14") (pinfunction "B14_B14") (pintype "passive"))
    )
    (net (code "265") (name "unconnected-(J3-PadB15)") (class "Default")
      (node (ref "J3") (pin "B15") (pinfunction "B15_B15") (pintype "passive"))
    )
    (net (code "266") (name "unconnected-(J3-PadB16)") (class "Default")
      (node (ref "J3") (pin "B16") (pinfunction "B16_B16") (pintype "passive"))
    )
    (net (code "267") (name "unconnected-(J3-PadB17)") (class "Default")
      (node (ref "J3") (pin "B17") (pinfunction "B17_B17") (pintype "passive"))
    )
    (net (code "268") (name "unconnected-(J3-PadB18)") (class "Default")
      (node (ref "J3") (pin "B18") (pinfunction "B18_B18") (pintype "passive"))
    )
    (net (code "269") (name "unconnected-(J3-PadB19)") (class "Default")
      (node (ref "J3") (pin "B19") (pinfunction "B19_B19") (pintype "passive"))
    )
    (net (code "270") (name "unconnected-(J3-PadB25)") (class "Default")
      (node (ref "J3") (pin "B25") (pinfunction "B25_B25") (pintype "passive"))
    )
    (net (code "271") (name "unconnected-(J3-PadB28)") (class "Default")
      (node (ref "J3") (pin "B28") (pinfunction "B28_B28") (pintype "passive"))
    )
    (net (code "272") (name "unconnected-(J3-PadB29)") (class "Default")
      (node (ref "J3") (pin "B29") (pinfunction "B29_B29") (pintype "passive"))
    )
    (net (code "273") (name "unconnected-(J3-PadB30)") (class "Default")
      (node (ref "J3") (pin "B30") (pinfunction "B30_B30") (pintype "passive"))
    )
    (net (code "274") (name "unconnected-(J3-PadB32)") (class "Default")
      (node (ref "J3") (pin "B32") (pinfunction "B32_B32") (pintype "passive"))
    )
    (net (code "275") (name "unconnected-(J3-PadB34)") (class "Default")
      (node (ref "J3") (pin "B34") (pinfunction "B34_B34") (pintype "passive"))
    )
    (net (code "276") (name "unconnected-(J3-PadB36)") (class "Default")
      (node (ref "J3") (pin "B36") (pinfunction "B36_B36") (pintype "passive"))
    )
    (net (code "277") (name "unconnected-(J3-PadB38)") (class "Default")
      (node (ref "J3") (pin "B38") (pinfunction "B38_B38") (pintype "passive"))
    )
    (net (code "278") (name "unconnected-(J3-PadE11)") (class "Default")
      (node (ref "J3") (pin "E11") (pinfunction "E11_E11") (pintype "passive"))
    )
    (net (code "279") (name "unconnected-(J3-PadE12)") (class "Default")
      (node (ref "J3") (pin "E12") (pinfunction "E12_E12") (pintype "passive"))
    )
    (net (code "280") (name "unconnected-(J3-PadE13)") (class "Default")
      (node (ref "J3") (pin "E13") (pinfunction "E13_E13") (pintype "passive"))
    )
    (net (code "281") (name "unconnected-(J3-PadE14)") (class "Default")
      (node (ref "J3") (pin "E14") (pinfunction "E14_E14") (pintype "passive"))
    )
    (net (code "282") (name "unconnected-(J3-PadE15)") (class "Default")
      (node (ref "J3") (pin "E15") (pinfunction "E15_E15") (pintype "passive"))
    )
    (net (code "283") (name "unconnected-(J3-PadE16)") (class "Default")
      (node (ref "J3") (pin "E16") (pinfunction "E16_E16") (pintype "passive"))
    )
    (net (code "284") (name "unconnected-(J3-PadE17)") (class "Default")
      (node (ref "J3") (pin "E17") (pinfunction "E17_E17") (pintype "passive"))
    )
    (net (code "285") (name "unconnected-(J3-PadE18)") (class "Default")
      (node (ref "J3") (pin "E18") (pinfunction "E18_E18") (pintype "passive"))
    )
    (net (code "286") (name "unconnected-(J3-PadE19)") (class "Default")
      (node (ref "J3") (pin "E19") (pinfunction "E19_E19") (pintype "passive"))
    )
    (net (code "287") (name "unconnected-(J3-PadE29)") (class "Default")
      (node (ref "J3") (pin "E29") (pinfunction "E29_E29") (pintype "passive"))
    )
    (net (code "288") (name "unconnected-(J3-PadE30)") (class "Default")
      (node (ref "J3") (pin "E30") (pinfunction "E30_E30") (pintype "passive"))
    )
    (net (code "289") (name "unconnected-(J3-PadE31)") (class "Default")
      (node (ref "J3") (pin "E31") (pinfunction "E31_E31") (pintype "passive"))
    )
    (net (code "290") (name "unconnected-(J3-PadE32)") (class "Default")
      (node (ref "J3") (pin "E32") (pinfunction "E32_E32") (pintype "passive"))
    )
    (net (code "291") (name "unconnected-(J3-PadE33)") (class "Default")
      (node (ref "J3") (pin "E33") (pinfunction "E33_E33") (pintype "passive"))
    )
    (net (code "292") (name "unconnected-(J3-PadE34)") (class "Default")
      (node (ref "J3") (pin "E34") (pinfunction "E34_E34") (pintype "passive"))
    )
    (net (code "293") (name "unconnected-(J3-PadE35)") (class "Default")
      (node (ref "J3") (pin "E35") (pinfunction "E35_E35") (pintype "passive"))
    )
    (net (code "294") (name "unconnected-(J3-PadE36)") (class "Default")
      (node (ref "J3") (pin "E36") (pinfunction "E36_E36") (pintype "passive"))
    )
    (net (code "295") (name "unconnected-(J3-PadE37)") (class "Default")
      (node (ref "J3") (pin "E37") (pinfunction "E37_E37") (pintype "passive"))
    )
    (net (code "296") (name "unconnected-(J3-PadE38)") (class "Default")
      (node (ref "J3") (pin "E38") (pinfunction "E38_E38") (pintype "passive"))
    )
    (net (code "297") (name "unconnected-(J3-PadE39)") (class "Default")
      (node (ref "J3") (pin "E39") (pinfunction "E39_E39") (pintype "passive"))
    )
    (net (code "298") (name "unconnected-(J3-PadE40)") (class "Default")
      (node (ref "J3") (pin "E40") (pinfunction "E40_E40") (pintype "passive"))
    )
    (net (code "299") (name "unconnected-(J3-PadF11)") (class "Default")
      (node (ref "J3") (pin "F11") (pinfunction "F11_F11") (pintype "passive"))
    )
    (net (code "300") (name "unconnected-(J3-PadF12)") (class "Default")
      (node (ref "J3") (pin "F12") (pinfunction "F12_F12") (pintype "passive"))
    )
    (net (code "301") (name "unconnected-(J3-PadF13)") (class "Default")
      (node (ref "J3") (pin "F13") (pinfunction "F13_F13") (pintype "passive"))
    )
    (net (code "302") (name "unconnected-(J3-PadF14)") (class "Default")
      (node (ref "J3") (pin "F14") (pinfunction "F14_F14") (pintype "passive"))
    )
    (net (code "303") (name "unconnected-(J3-PadF15)") (class "Default")
      (node (ref "J3") (pin "F15") (pinfunction "F15_F15") (pintype "passive"))
    )
    (net (code "304") (name "unconnected-(J3-PadF16)") (class "Default")
      (node (ref "J3") (pin "F16") (pinfunction "F16_F16") (pintype "passive"))
    )
    (net (code "305") (name "unconnected-(J3-PadF17)") (class "Default")
      (node (ref "J3") (pin "F17") (pinfunction "F17_F17") (pintype "passive"))
    )
    (net (code "306") (name "unconnected-(J3-PadF18)") (class "Default")
      (node (ref "J3") (pin "F18") (pinfunction "F18_F18") (pintype "passive"))
    )
    (net (code "307") (name "unconnected-(J3-PadF19)") (class "Default")
      (node (ref "J3") (pin "F19") (pinfunction "F19_F19") (pintype "passive"))
    )
    (net (code "308") (name "unconnected-(J3-PadF29)") (class "Default")
      (node (ref "J3") (pin "F29") (pinfunction "F29_F29") (pintype "passive"))
    )
    (net (code "309") (name "unconnected-(J3-PadF30)") (class "Default")
      (node (ref "J3") (pin "F30") (pinfunction "F30_F30") (pintype "passive"))
    )
    (net (code "310") (name "unconnected-(J3-PadF31)") (class "Default")
      (node (ref "J3") (pin "F31") (pinfunction "F31_F31") (pintype "passive"))
    )
    (net (code "311") (name "unconnected-(J3-PadF32)") (class "Default")
      (node (ref "J3") (pin "F32") (pinfunction "F32_F32") (pintype "passive"))
    )
    (net (code "312") (name "unconnected-(J3-PadF33)") (class "Default")
      (node (ref "J3") (pin "F33") (pinfunction "F33_F33") (pintype "passive"))
    )
    (net (code "313") (name "unconnected-(J3-PadF34)") (class "Default")
      (node (ref "J3") (pin "F34") (pinfunction "F34_F34") (pintype "passive"))
    )
    (net (code "314") (name "unconnected-(J3-PadF35)") (class "Default")
      (node (ref "J3") (pin "F35") (pinfunction "F35_F35") (pintype "passive"))
    )
    (net (code "315") (name "unconnected-(J3-PadF36)") (class "Default")
      (node (ref "J3") (pin "F36") (pinfunction "F36_F36") (pintype "passive"))
    )
    (net (code "316") (name "unconnected-(J3-PadF37)") (class "Default")
      (node (ref "J3") (pin "F37") (pinfunction "F37_F37") (pintype "passive"))
    )
    (net (code "317") (name "unconnected-(J3-PadF38)") (class "Default")
      (node (ref "J3") (pin "F38") (pinfunction "F38_F38") (pintype "passive"))
    )
    (net (code "318") (name "unconnected-(J3-PadF39)") (class "Default")
      (node (ref "J3") (pin "F39") (pinfunction "F39_F39") (pintype "passive"))
    )
    (net (code "319") (name "unconnected-(J3-PadF40)") (class "Default")
      (node (ref "J3") (pin "F40") (pinfunction "F40_F40") (pintype "passive"))
    )
    (net (code "320") (name "unconnected-(P1-Pad27)") (class "Default")
      (node (ref "P1") (pin "27") (pinfunction "27_27") (pintype "passive"))
    )
    (net (code "321") (name "unconnected-(P1-Pad28)") (class "Default")
      (node (ref "P1") (pin "28") (pinfunction "28_28") (pintype "passive"))
    )
    (net (code "322") (name "unconnected-(P1-Pad29)") (class "Default")
      (node (ref "P1") (pin "29") (pinfunction "29_29") (pintype "passive"))
    )
    (net (code "323") (name "unconnected-(P1-Pad30)") (class "Default")
      (node (ref "P1") (pin "30") (pinfunction "30_30") (pintype "passive"))
    )
    (net (code "324") (name "unconnected-(P1-Pad31)") (class "Default")
      (node (ref "P1") (pin "31") (pinfunction "31_31") (pintype "passive"))
    )
    (net (code "325") (name "unconnected-(P1-Pad32)") (class "Default")
      (node (ref "P1") (pin "32") (pinfunction "32_32") (pintype "passive"))
    )
    (net (code "326") (name "unconnected-(P1-Pad33)") (class "Default")
      (node (ref "P1") (pin "33") (pinfunction "33_33") (pintype "passive"))
    )
    (net (code "327") (name "unconnected-(P1-Pad34)") (class "Default")
      (node (ref "P1") (pin "34") (pinfunction "34_34") (pintype "passive"))
    )
    (net (code "328") (name "unconnected-(P1-Pad35)") (class "Default")
      (node (ref "P1") (pin "35") (pinfunction "35_35") (pintype "passive"))
    )
    (net (code "329") (name "unconnected-(P1-Pad36)") (class "Default")
      (node (ref "P1") (pin "36") (pinfunction "36_36") (pintype "passive"))
    )
    (net (code "330") (name "unconnected-(P1-Pad37)") (class "Default")
      (node (ref "P1") (pin "37") (pinfunction "37_37") (pintype "passive"))
    )
    (net (code "331") (name "unconnected-(P1-Pad38)") (class "Default")
      (node (ref "P1") (pin "38") (pinfunction "38_38") (pintype "passive"))
    )
    (net (code "332") (name "unconnected-(P1-Pad39)") (class "Default")
      (node (ref "P1") (pin "39") (pinfunction "39_39") (pintype "passive"))
    )
    (net (code "333") (name "unconnected-(P1-Pad40)") (class "Default")
      (node (ref "P1") (pin "40") (pinfunction "40_40") (pintype "passive"))
    )
  )
)
